# KMT1-42_CPU_rev_2_0_0.net
KiCad netlist of a schematic drawn in Altium Designer
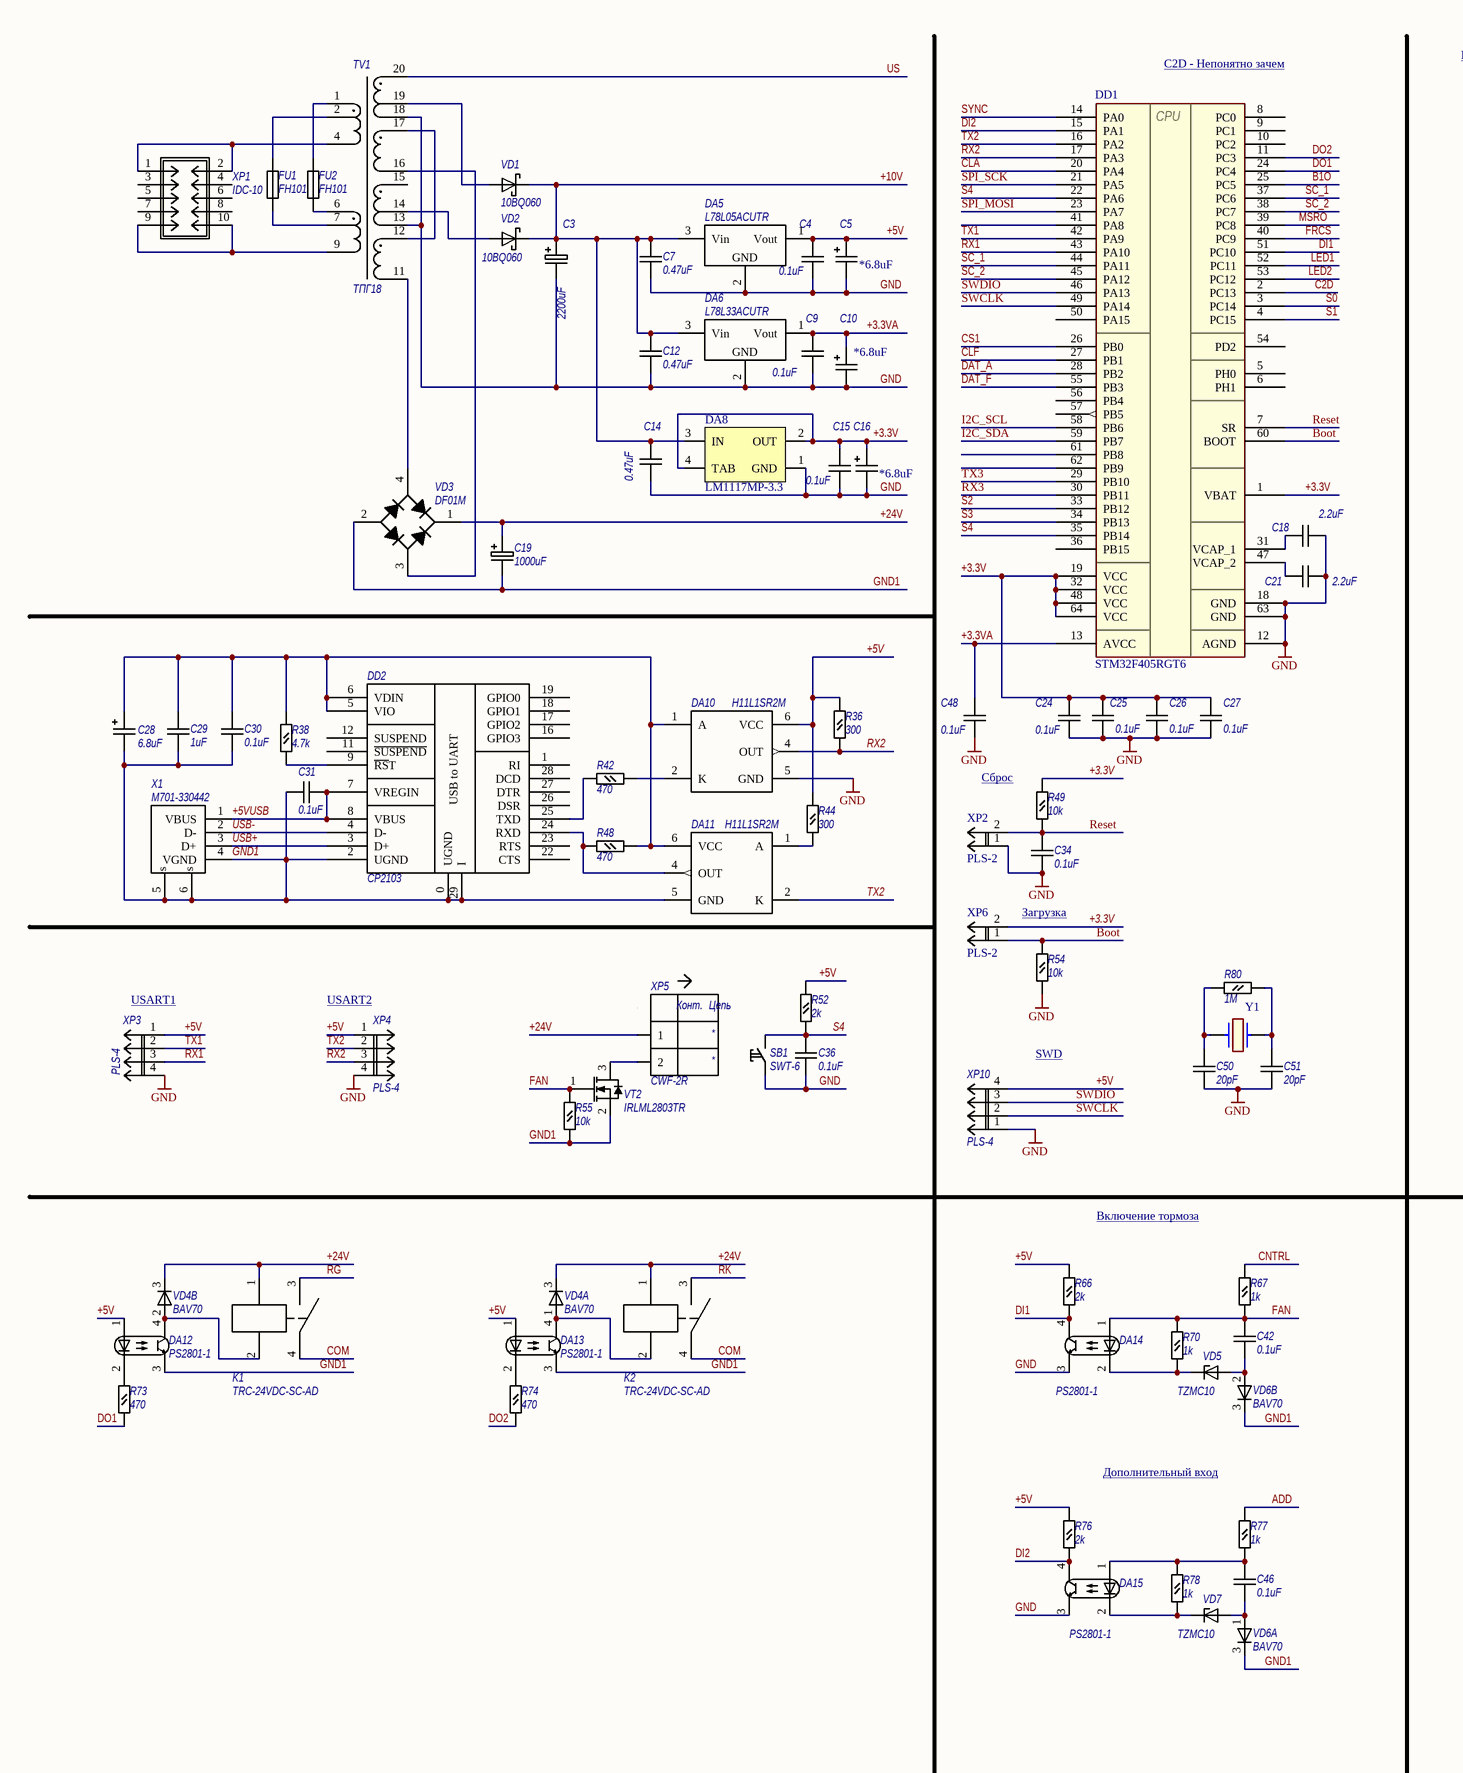
[diagram p0: KMT1-42.CPU rev.2.0.0.SchDoc, left]
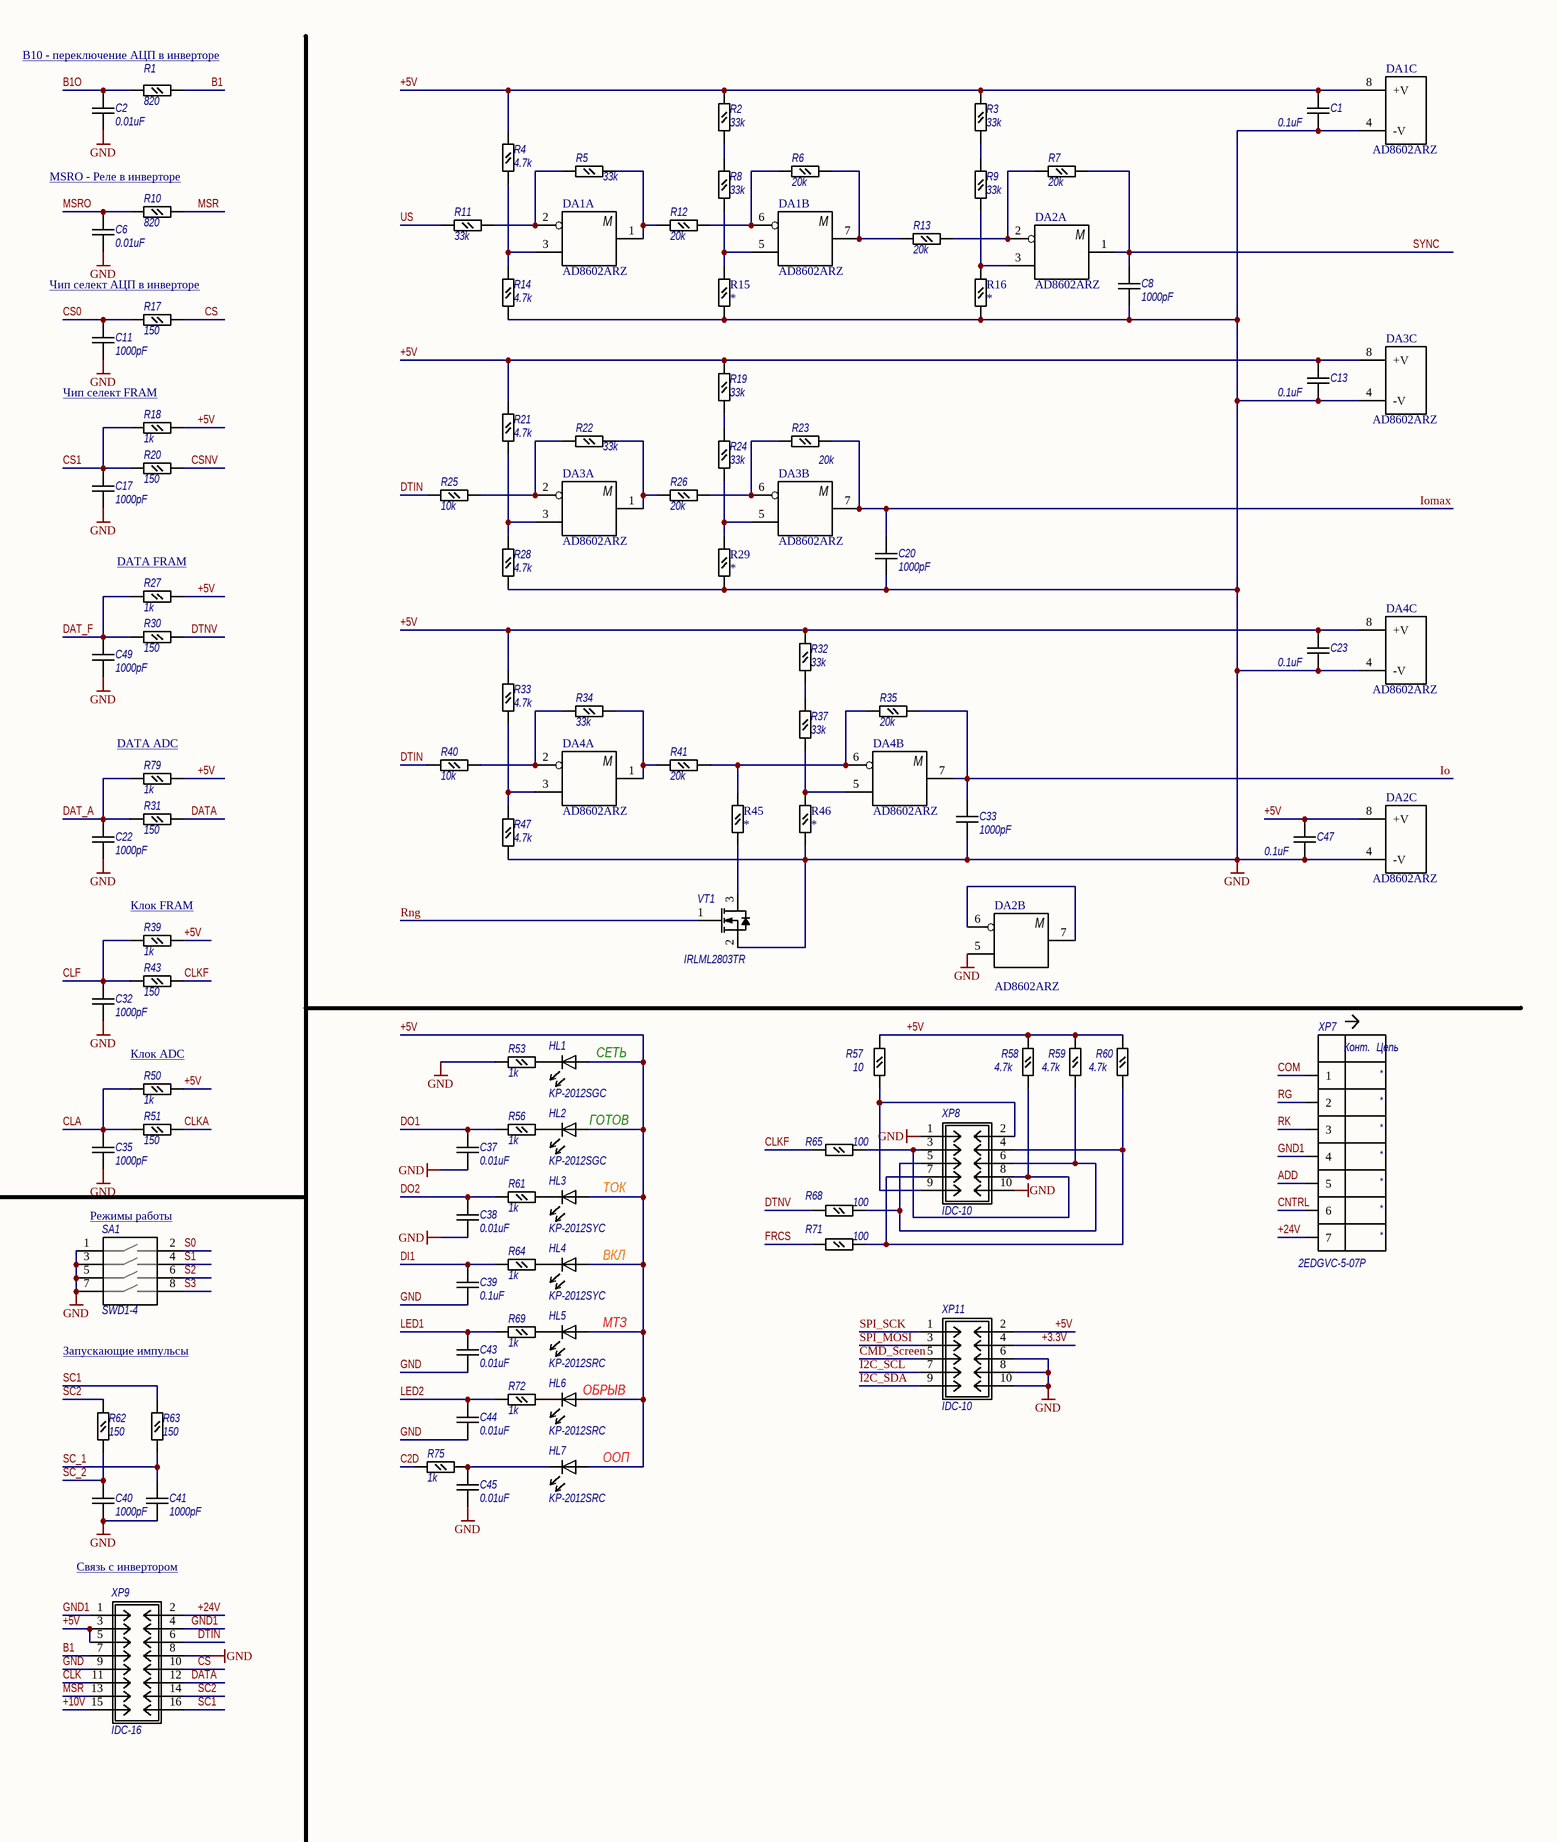
[diagram p1: KMT1-42.CPU rev.2.0.0.SchDoc, right]

(export (version "E")
  (design (tool "Eeschema 10.0.6"))
  (components
    (comp (ref "C1")
      (value "0.1uF")
      (footprint "cap0805")
      (description "Керамический конденсатор, SMD")
      (fields
        (field (name "PART NUMBER") "cap0805")
        (field (name "VALUESCH") "0.1uF")
        (field (name "TOLERANCE") "X7R")
      )
      (libsource (lib "db_imd") (part "Cap"))
    )
    (comp (ref "C2")
      (value "0.01uF")
      (footprint "cap0805")
      (description "Керамический конденсатор, SMD")
      (fields
        (field (name "PART NUMBER") "cap0805")
        (field (name "VALUESCH") "0.01uF")
        (field (name "TOLERANCE") "X7R")
      )
      (libsource (lib "db_imd") (part "Cap"))
    )
    (comp (ref "C3")
      (value "2200uF")
      (footprint "ECR-EHR 13mm")
      (description "Алюминиевый конденсатор Hitano")
      (fields
        (field (name "PART NUMBER") "ECR/EHR/EXR D=13mm")
        (field (name "VALUESCH") "2200uF")
        (field (name "VOLTAGE") "16V")
      )
      (libsource (lib "db_imd") (part "cap_elect_pol"))
    )
    (comp (ref "C4")
      (value "0.1uF")
      (footprint "cap0805")
      (description "Керамический конденсатор, SMD")
      (fields
        (field (name "PART NUMBER") "cap0805")
        (field (name "VALUESCH") "0.1uF")
        (field (name "TOLERANCE") "X7R")
      )
      (libsource (lib "db_imd") (part "Cap"))
    )
    (comp (ref "C5")
      (value "*6.8uF")
      (footprint "TC3216-1206-A")
      (description "Танталовый конденсатор, SMD")
      (fields (field (name "PART NUMBER") "capA") (field (name "VALUESCH") "*6.8uF"))
      (libsource (lib "db_imd") (part "Cap_el"))
    )
    (comp (ref "C6")
      (value "0.01uF")
      (footprint "cap0805")
      (description "Керамический конденсатор, SMD")
      (fields
        (field (name "PART NUMBER") "cap0805")
        (field (name "VALUESCH") "0.01uF")
        (field (name "TOLERANCE") "X7R")
      )
      (libsource (lib "db_imd") (part "Cap"))
    )
    (comp (ref "C7")
      (value "0.47uF")
      (footprint "cap0805")
      (description "Керамический конденсатор, SMD")
      (fields
        (field (name "PART NUMBER") "cap0805")
        (field (name "VALUESCH") "0.47uF")
        (field (name "TOLERANCE") "X7R")
      )
      (libsource (lib "db_imd") (part "Cap"))
    )
    (comp (ref "C8")
      (value "1000pF")
      (footprint "cap0805")
      (description "Керамический конденсатор, SMD")
      (fields
        (field (name "PART NUMBER") "cap0805")
        (field (name "VALUESCH") "1000pF")
        (field (name "TOLERANCE") "X7R")
      )
      (libsource (lib "db_imd") (part "Cap"))
    )
    (comp (ref "C9")
      (value "0.1uF")
      (footprint "cap0805")
      (description "Керамический конденсатор, SMD")
      (fields
        (field (name "PART NUMBER") "cap0805")
        (field (name "VALUESCH") "0.1uF")
        (field (name "TOLERANCE") "X7R")
      )
      (libsource (lib "db_imd") (part "Cap"))
    )
    (comp (ref "C10")
      (value "*6.8uF")
      (footprint "TC3216-1206-A")
      (description "Танталовый конденсатор, SMD")
      (fields (field (name "PART NUMBER") "capA") (field (name "VALUESCH") "*6.8uF"))
      (libsource (lib "db_imd") (part "Cap_el"))
    )
    (comp (ref "C11")
      (value "1000pF")
      (footprint "cap0805")
      (description "Керамический конденсатор, SMD")
      (fields
        (field (name "PART NUMBER") "cap0805")
        (field (name "VALUESCH") "1000pF")
        (field (name "TOLERANCE") "X7R")
      )
      (libsource (lib "db_imd") (part "Cap"))
    )
    (comp (ref "C12")
      (value "0.47uF")
      (footprint "cap0805")
      (description "Керамический конденсатор, SMD")
      (fields
        (field (name "PART NUMBER") "cap0805")
        (field (name "VALUESCH") "0.47uF")
        (field (name "TOLERANCE") "X7R")
      )
      (libsource (lib "db_imd") (part "Cap"))
    )
    (comp (ref "C13")
      (value "0.1uF")
      (footprint "cap0805")
      (description "Керамический конденсатор, SMD")
      (fields
        (field (name "PART NUMBER") "cap0805")
        (field (name "VALUESCH") "0.1uF")
        (field (name "TOLERANCE") "X7R")
      )
      (libsource (lib "db_imd") (part "Cap"))
    )
    (comp (ref "C14")
      (value "0.47uF")
      (footprint "cap0805")
      (description "Керамический конденсатор, SMD")
      (fields
        (field (name "PART NUMBER") "cap0805")
        (field (name "VALUESCH") "0.47uF")
        (field (name "TOLERANCE") "X7R")
      )
      (libsource (lib "db_imd") (part "Cap"))
    )
    (comp (ref "C15")
      (value "0.1uF")
      (footprint "cap0805")
      (description "Керамический конденсатор, SMD")
      (fields
        (field (name "PART NUMBER") "cap0805")
        (field (name "VALUESCH") "0.1uF")
        (field (name "TOLERANCE") "X7R")
      )
      (libsource (lib "db_imd") (part "Cap"))
    )
    (comp (ref "C16")
      (value "*6.8uF")
      (footprint "TC3216-1206-A")
      (description "Танталовый конденсатор, SMD")
      (fields (field (name "PART NUMBER") "capA") (field (name "VALUESCH") "*6.8uF"))
      (libsource (lib "db_imd") (part "Cap_el"))
    )
    (comp (ref "C17")
      (value "1000pF")
      (footprint "cap0805")
      (description "Керамический конденсатор, SMD")
      (fields
        (field (name "PART NUMBER") "cap0805")
        (field (name "VALUESCH") "1000pF")
        (field (name "TOLERANCE") "X7R")
      )
      (libsource (lib "db_imd") (part "Cap"))
    )
    (comp (ref "C18")
      (value "2.2uF")
      (footprint "cap0805")
      (description "Керамический конденсатор, SMD")
      (fields
        (field (name "PART NUMBER") "cap0805")
        (field (name "VALUESCH") "2.2uF")
        (field (name "TOLERANCE") "X7R")
      )
      (libsource (lib "db_imd") (part "Cap"))
    )
    (comp (ref "C19")
      (value "1000uF")
      (footprint "ECR-EHR 13mm")
      (description "Алюминиевый конденсатор Hitano")
      (fields
        (field (name "PART NUMBER") "ECR/EHR/EXR D=13mm")
        (field (name "VALUESCH") "1000uF")
        (field (name "VOLTAGE") "35V")
      )
      (libsource (lib "db_imd") (part "cap_elect_pol"))
    )
    (comp (ref "C20")
      (value "1000pF")
      (footprint "cap0805")
      (description "Керамический конденсатор, SMD")
      (fields
        (field (name "PART NUMBER") "cap0805")
        (field (name "VALUESCH") "1000pF")
        (field (name "TOLERANCE") "X7R")
      )
      (libsource (lib "db_imd") (part "Cap"))
    )
    (comp (ref "C21")
      (value "2.2uF")
      (footprint "cap0805")
      (description "Керамический конденсатор, SMD")
      (fields
        (field (name "PART NUMBER") "cap0805")
        (field (name "VALUESCH") "2.2uF")
        (field (name "TOLERANCE") "X7R")
      )
      (libsource (lib "db_imd") (part "Cap"))
    )
    (comp (ref "C22")
      (value "1000pF")
      (footprint "cap0805")
      (description "Керамический конденсатор, SMD")
      (fields
        (field (name "PART NUMBER") "cap0805")
        (field (name "VALUESCH") "1000pF")
        (field (name "TOLERANCE") "X7R")
      )
      (libsource (lib "db_imd") (part "Cap"))
    )
    (comp (ref "C23")
      (value "0.1uF")
      (footprint "cap0805")
      (description "Керамический конденсатор, SMD")
      (fields
        (field (name "PART NUMBER") "cap0805")
        (field (name "VALUESCH") "0.1uF")
        (field (name "TOLERANCE") "X7R")
      )
      (libsource (lib "db_imd") (part "Cap"))
    )
    (comp (ref "C24")
      (value "0.1uF")
      (footprint "cap0805")
      (description "Керамический конденсатор, SMD")
      (fields
        (field (name "PART NUMBER") "cap0805")
        (field (name "VALUESCH") "0.1uF")
        (field (name "TOLERANCE") "X7R")
      )
      (libsource (lib "db_imd") (part "Cap"))
    )
    (comp (ref "C25")
      (value "0.1uF")
      (footprint "cap0805")
      (description "Керамический конденсатор, SMD")
      (fields
        (field (name "PART NUMBER") "cap0805")
        (field (name "VALUESCH") "0.1uF")
        (field (name "TOLERANCE") "X7R")
      )
      (libsource (lib "db_imd") (part "Cap"))
    )
    (comp (ref "C26")
      (value "0.1uF")
      (footprint "cap0805")
      (description "Керамический конденсатор, SMD")
      (fields
        (field (name "PART NUMBER") "cap0805")
        (field (name "VALUESCH") "0.1uF")
        (field (name "TOLERANCE") "X7R")
      )
      (libsource (lib "db_imd") (part "Cap"))
    )
    (comp (ref "C27")
      (value "0.1uF")
      (footprint "cap0805")
      (description "Керамический конденсатор, SMD")
      (fields
        (field (name "PART NUMBER") "cap0805")
        (field (name "VALUESCH") "0.1uF")
        (field (name "TOLERANCE") "X7R")
      )
      (libsource (lib "db_imd") (part "Cap"))
    )
    (comp (ref "C28")
      (value "6.8uF")
      (footprint "TC3216-1206-A")
      (description "Танталовый конденсатор, SMD")
      (fields
        (field (name "PART NUMBER") "capA")
        (field (name "VALUESCH") "6.8uF")
        (field (name "VOLTAGE") "6.3V")
      )
      (libsource (lib "db_imd") (part "Cap_el"))
    )
    (comp (ref "C29")
      (value "1uF")
      (footprint "cap0805")
      (description "Керамический конденсатор, SMD")
      (fields
        (field (name "PART NUMBER") "cap0805")
        (field (name "VALUESCH") "1uF")
        (field (name "TOLERANCE") "X7R")
      )
      (libsource (lib "db_imd") (part "Cap"))
    )
    (comp (ref "C30")
      (value "0.1uF")
      (footprint "cap0805")
      (description "Керамический конденсатор, SMD")
      (fields
        (field (name "PART NUMBER") "cap0805")
        (field (name "VALUESCH") "0.1uF")
        (field (name "TOLERANCE") "X7R")
      )
      (libsource (lib "db_imd") (part "Cap"))
    )
    (comp (ref "C31")
      (value "0.1uF")
      (footprint "cap0805")
      (description "Керамический конденсатор, SMD")
      (fields
        (field (name "PART NUMBER") "cap0805")
        (field (name "VALUESCH") "0.1uF")
        (field (name "TOLERANCE") "X7R")
      )
      (libsource (lib "db_imd") (part "Cap"))
    )
    (comp (ref "C32")
      (value "1000pF")
      (footprint "cap0805")
      (description "Керамический конденсатор, SMD")
      (fields
        (field (name "PART NUMBER") "cap0805")
        (field (name "VALUESCH") "1000pF")
        (field (name "TOLERANCE") "X7R")
      )
      (libsource (lib "db_imd") (part "Cap"))
    )
    (comp (ref "C33")
      (value "1000pF")
      (footprint "cap0805")
      (description "Керамический конденсатор, SMD")
      (fields
        (field (name "PART NUMBER") "cap0805")
        (field (name "VALUESCH") "1000pF")
        (field (name "TOLERANCE") "X7R")
      )
      (libsource (lib "db_imd") (part "Cap"))
    )
    (comp (ref "C34")
      (value "0.1uF")
      (footprint "cap0805")
      (description "Керамический конденсатор, SMD")
      (fields
        (field (name "PART NUMBER") "cap0805")
        (field (name "VALUESCH") "0.1uF")
        (field (name "TOLERANCE") "X7R")
      )
      (libsource (lib "db_imd") (part "Cap"))
    )
    (comp (ref "C35")
      (value "1000pF")
      (footprint "cap0805")
      (description "Керамический конденсатор, SMD")
      (fields
        (field (name "PART NUMBER") "cap0805")
        (field (name "VALUESCH") "1000pF")
        (field (name "TOLERANCE") "X7R")
      )
      (libsource (lib "db_imd") (part "Cap"))
    )
    (comp (ref "C36")
      (value "0.1uF")
      (footprint "cap0805")
      (description "Керамический конденсатор, SMD")
      (fields
        (field (name "PART NUMBER") "cap0805")
        (field (name "VALUESCH") "0.1uF")
        (field (name "TOLERANCE") "X7R")
      )
      (libsource (lib "db_imd") (part "Cap"))
    )
    (comp (ref "C37")
      (value "0.01uF")
      (footprint "cap0805")
      (description "Керамический конденсатор, SMD")
      (fields
        (field (name "PART NUMBER") "cap0805")
        (field (name "VALUESCH") "0.01uF")
        (field (name "TOLERANCE") "X7R")
      )
      (libsource (lib "db_imd") (part "Cap"))
    )
    (comp (ref "C38")
      (value "0.01uF")
      (footprint "cap0805")
      (description "Керамический конденсатор, SMD")
      (fields
        (field (name "PART NUMBER") "cap0805")
        (field (name "VALUESCH") "0.01uF")
        (field (name "TOLERANCE") "X7R")
      )
      (libsource (lib "db_imd") (part "Cap"))
    )
    (comp (ref "C39")
      (value "0.1uF")
      (footprint "cap0805")
      (description "Керамический конденсатор, SMD")
      (fields
        (field (name "PART NUMBER") "cap0805")
        (field (name "VALUESCH") "0.1uF")
        (field (name "TOLERANCE") "X7R")
      )
      (libsource (lib "db_imd") (part "Cap"))
    )
    (comp (ref "C40")
      (value "1000pF")
      (footprint "cap0805")
      (description "Керамический конденсатор, SMD")
      (fields
        (field (name "PART NUMBER") "cap0805")
        (field (name "VALUESCH") "1000pF")
        (field (name "TOLERANCE") "X7R")
      )
      (libsource (lib "db_imd") (part "Cap"))
    )
    (comp (ref "C41")
      (value "1000pF")
      (footprint "cap0805")
      (description "Керамический конденсатор, SMD")
      (fields
        (field (name "PART NUMBER") "cap0805")
        (field (name "VALUESCH") "1000pF")
        (field (name "TOLERANCE") "X7R")
      )
      (libsource (lib "db_imd") (part "Cap"))
    )
    (comp (ref "C42")
      (value "0.1uF")
      (footprint "cap0805")
      (description "Керамический конденсатор, SMD")
      (fields
        (field (name "PART NUMBER") "cap0805")
        (field (name "VALUESCH") "0.1uF")
        (field (name "TOLERANCE") "X7R")
      )
      (libsource (lib "db_imd") (part "Cap"))
    )
    (comp (ref "C43")
      (value "0.01uF")
      (footprint "cap0805")
      (description "Керамический конденсатор, SMD")
      (fields
        (field (name "PART NUMBER") "cap0805")
        (field (name "VALUESCH") "0.01uF")
        (field (name "TOLERANCE") "X7R")
      )
      (libsource (lib "db_imd") (part "Cap"))
    )
    (comp (ref "C44")
      (value "0.01uF")
      (footprint "cap0805")
      (description "Керамический конденсатор, SMD")
      (fields
        (field (name "PART NUMBER") "cap0805")
        (field (name "VALUESCH") "0.01uF")
        (field (name "TOLERANCE") "X7R")
      )
      (libsource (lib "db_imd") (part "Cap"))
    )
    (comp (ref "C45")
      (value "0.01uF")
      (footprint "cap0805")
      (description "Керамический конденсатор, SMD")
      (fields
        (field (name "PART NUMBER") "cap0805")
        (field (name "VALUESCH") "0.01uF")
        (field (name "TOLERANCE") "X7R")
      )
      (libsource (lib "db_imd") (part "Cap"))
    )
    (comp (ref "C46")
      (value "0.1uF")
      (footprint "cap0805")
      (description "Керамический конденсатор, SMD")
      (fields
        (field (name "PART NUMBER") "cap0805")
        (field (name "VALUESCH") "0.1uF")
        (field (name "TOLERANCE") "X7R")
      )
      (libsource (lib "db_imd") (part "Cap"))
    )
    (comp (ref "C47")
      (value "0.1uF")
      (footprint "cap0805")
      (description "Керамический конденсатор, SMD")
      (fields
        (field (name "PART NUMBER") "cap0805")
        (field (name "VALUESCH") "0.1uF")
        (field (name "TOLERANCE") "X7R")
      )
      (libsource (lib "db_imd") (part "Cap"))
    )
    (comp (ref "C48")
      (value "0.1uF")
      (footprint "cap0805")
      (description "Керамический конденсатор, SMD")
      (fields
        (field (name "PART NUMBER") "cap0805")
        (field (name "VALUESCH") "0.1uF")
        (field (name "TOLERANCE") "X7R")
      )
      (libsource (lib "db_imd") (part "Cap"))
    )
    (comp (ref "C49")
      (value "1000pF")
      (footprint "cap0805")
      (description "Керамический конденсатор, SMD")
      (fields
        (field (name "PART NUMBER") "cap0805")
        (field (name "VALUESCH") "1000pF")
        (field (name "TOLERANCE") "X7R")
      )
      (libsource (lib "db_imd") (part "Cap"))
    )
    (comp (ref "C50")
      (value "20pF")
      (footprint "cap0805")
      (description "Керамический конденсатор, SMD")
      (fields
        (field (name "PART NUMBER") "cap0805")
        (field (name "VALUESCH") "20pF")
        (field (name "TOLERANCE") "X7R")
      )
      (libsource (lib "db_imd") (part "Cap"))
    )
    (comp (ref "C51")
      (value "20pF")
      (footprint "cap0805")
      (description "Керамический конденсатор, SMD")
      (fields
        (field (name "PART NUMBER") "cap0805")
        (field (name "VALUESCH") "20pF")
        (field (name "TOLERANCE") "X7R")
      )
      (libsource (lib "db_imd") (part "Cap"))
    )
    (comp (ref "DA1")
      (value "AD8602ARZ")
      (footprint "SO-8")
      (description "Операционный усилитель 2 в 1")
      (fields (field (name "VALUESCH") "AD8602ARZ"))
      (libsource (lib "db_imd") (part "Opamp2x1"))
    )
    (comp (ref "DA2")
      (value "AD8602ARZ")
      (footprint "SO-8")
      (description "Операционный усилитель 2 в 1")
      (fields (field (name "VALUESCH") "AD8602ARZ"))
      (libsource (lib "db_imd") (part "Opamp2x1"))
    )
    (comp (ref "DA3")
      (value "AD8602ARZ")
      (footprint "SO-8")
      (description "Операционный усилитель 2 в 1")
      (fields (field (name "VALUESCH") "AD8602ARZ"))
      (libsource (lib "db_imd") (part "Opamp2x1"))
    )
    (comp (ref "DA4")
      (value "AD8602ARZ")
      (footprint "SO-8")
      (description "Операционный усилитель 2 в 1")
      (fields (field (name "VALUESCH") "AD8602ARZ"))
      (libsource (lib "db_imd") (part "Opamp2x1"))
    )
    (comp (ref "DA5")
      (value "L78L05ACUTR")
      (footprint "SOT89")
      (description "Линейный стабилизатор 5V")
      (fields (field (name "VALUESCH") "L78L05ACUTR"))
      (libsource (lib "db_imd") (part "L78L00"))
    )
    (comp (ref "DA6")
      (value "L78L33ACUTR")
      (footprint "SOT89")
      (description "Линейный стабилизатор 3.3V")
      (fields (field (name "VALUESCH") "L78L33ACUTR"))
      (libsource (lib "db_imd") (part "L78L00"))
    )
    (comp (ref "DA8")
      (value "LM1117MP-3.3")
      (footprint "SOT223")
      (description "Линейный стабилизатор 3.3V")
      (fields (field (name "VALUESCH") "LM1117MP-3.3"))
      (libsource (lib "db_intmash") (part "LM1117-3.3"))
    )
    (comp (ref "DA10")
      (value "H11L1SR2M")
      (footprint "PDIP6")
      (description "Оптопара 1 Мбит")
      (fields (field (name "VALUESCH") "H11L1SR2M"))
      (libsource (lib "db_imd") (part "H11L1SR2M"))
    )
    (comp (ref "DA11")
      (value "H11L1SR2M")
      (footprint "PDIP6")
      (description "Оптопара 1 Мбит")
      (fields (field (name "VALUESCH") "H11L1SR2M"))
      (libsource (lib "") (part "H11L1SR2M_1"))
    )
    (comp (ref "DA12")
      (value "PS2801-1")
      (footprint "SOP4")
      (description "Оптопара")
      (fields (field (name "VALUESCH") "PS2801-1"))
      (libsource (lib "") (part "PS2801-1_1"))
    )
    (comp (ref "DA13")
      (value "PS2801-1")
      (footprint "SOP4")
      (description "Оптопара")
      (fields (field (name "VALUESCH") "PS2801-1"))
      (libsource (lib "") (part "PS2801-1_1"))
    )
    (comp (ref "DA14")
      (value "PS2801-1")
      (footprint "SOP4")
      (description "Оптопара")
      (fields (field (name "VALUESCH") "PS2801-1"))
      (libsource (lib "db_imd") (part "PS2801-1"))
    )
    (comp (ref "DA15")
      (value "PS2801-1")
      (footprint "SOP4")
      (description "Оптопара")
      (fields (field (name "VALUESCH") "PS2801-1"))
      (libsource (lib "db_imd") (part "PS2801-1"))
    )
    (comp (ref "DD1")
      (value "STM32F405RGT6")
      (footprint "LQFP64")
      (description "Микроконтроллер 32 бит CORTEX M4")
      (fields (field (name "VALUESCH") "STM32F405RGT6"))
      (libsource (lib "db_imd") (part "STM32F405RGT6"))
    )
    (comp (ref "DD2")
      (value "CP2103")
      (footprint "QFN-28")
      (description "Чип USB -> UART")
      (fields (field (name "VALUESCH") "CP2103"))
      (libsource (lib "db_imd") (part "CP2103"))
    )
    (comp (ref "FU1")
      (value "FH101")
      (footprint "FH101")
      (description "Держатель для предохранителей 250В 5А")
      (fields (field (name "VALUESCH") "FH101"))
      (libsource (lib "db_imd") (part "FUSE"))
    )
    (comp (ref "FU2")
      (value "FH101")
      (footprint "FH101")
      (description "Держатель для предохранителей 250В 5А")
      (fields (field (name "VALUESCH") "FH101"))
      (libsource (lib "db_imd") (part "FUSE"))
    )
    (comp (ref "HL1")
      (value "KP-2012SGC")
      (footprint "Led0805")
      (description "SMD светодиод зеленый")
      (fields (field (name "VALUESCH") "KP-2012SGC"))
      (libsource (lib "db_imd") (part "LED"))
    )
    (comp (ref "HL2")
      (value "KP-2012SGC")
      (footprint "Led0805")
      (description "SMD светодиод зеленый")
      (fields (field (name "VALUESCH") "KP-2012SGC"))
      (libsource (lib "db_imd") (part "LED"))
    )
    (comp (ref "HL3")
      (value "KP-2012SYC")
      (footprint "Led0805")
      (description "SMD светодиод желтый")
      (fields (field (name "VALUESCH") "KP-2012SYC"))
      (libsource (lib "db_imd") (part "LED"))
    )
    (comp (ref "HL4")
      (value "KP-2012SYC")
      (footprint "Led0805")
      (description "SMD светодиод желтый")
      (fields (field (name "VALUESCH") "KP-2012SYC"))
      (libsource (lib "db_imd") (part "LED"))
    )
    (comp (ref "HL5")
      (value "KP-2012SRC")
      (footprint "Led0805")
      (description "SMD светодиод красный")
      (fields (field (name "VALUESCH") "KP-2012SRC"))
      (libsource (lib "db_imd") (part "LED"))
    )
    (comp (ref "HL6")
      (value "KP-2012SRC")
      (footprint "Led0805")
      (description "SMD светодиод красный")
      (fields (field (name "VALUESCH") "KP-2012SRC"))
      (libsource (lib "db_imd") (part "LED"))
    )
    (comp (ref "HL7")
      (value "KP-2012SRC")
      (footprint "Led0805")
      (description "SMD светодиод красный")
      (fields (field (name "VALUESCH") "KP-2012SRC"))
      (libsource (lib "db_imd") (part "LED"))
    )
    (comp (ref "K1")
      (value "TRC-24VDC-SC-AD")
      (footprint "TRC-24VDC-SC-AD")
      (description "Реле электромагнитное 24В 10А, 1 контакт (SPST)")
      (fields (field (name "VALUESCH") "TRC-24VDC-SC-AD"))
      (libsource (lib "db_imd") (part "SPST"))
    )
    (comp (ref "K2")
      (value "TRC-24VDC-SC-AD")
      (footprint "TRC-24VDC-SC-AD")
      (description "Реле электромагнитное 24В 10А, 1 контакт (SPST)")
      (fields (field (name "VALUESCH") "TRC-24VDC-SC-AD"))
      (libsource (lib "db_imd") (part "SPST"))
    )
    (comp (ref "R1")
      (value "820")
      (footprint "res0805")
      (description "Резистор 0.125 W, SMD")
      (fields (field (name "PART NUMBER") "res0805") (field (name "VALUESCH") "820"))
      (libsource (lib "db_imd") (part "res_0.125W"))
    )
    (comp (ref "R2")
      (value "33k")
      (footprint "res0805")
      (description "Резистор 0.125 W, SMD")
      (fields (field (name "PART NUMBER") "res0805") (field (name "VALUESCH") "33k"))
      (libsource (lib "") (part "res_0.125W_3"))
    )
    (comp (ref "R3")
      (value "33k")
      (footprint "res0805")
      (description "Резистор 0.125 W, SMD")
      (fields (field (name "PART NUMBER") "res0805") (field (name "VALUESCH") "33k"))
      (libsource (lib "") (part "res_0.125W_3"))
    )
    (comp (ref "R4")
      (value "4.7k")
      (footprint "res0805")
      (description "Резистор 0.125 W, SMD")
      (fields (field (name "PART NUMBER") "res0805") (field (name "VALUESCH") "4.7k"))
      (libsource (lib "") (part "res_0.125W_3"))
    )
    (comp (ref "R5")
      (value "33k")
      (footprint "res0805")
      (description "Резистор 0.125 W, SMD")
      (fields (field (name "PART NUMBER") "res0805") (field (name "VALUESCH") "33k"))
      (libsource (lib "db_imd") (part "res_0.125W"))
    )
    (comp (ref "R6")
      (value "20k")
      (footprint "res0805")
      (description "Резистор 0.125 W, SMD")
      (fields (field (name "PART NUMBER") "res0805") (field (name "VALUESCH") "20k"))
      (libsource (lib "db_imd") (part "res_0.125W"))
    )
    (comp (ref "R7")
      (value "20k")
      (footprint "res0805")
      (description "Резистор 0.125 W, SMD")
      (fields (field (name "PART NUMBER") "res0805") (field (name "VALUESCH") "20k"))
      (libsource (lib "db_imd") (part "res_0.125W"))
    )
    (comp (ref "R8")
      (value "33k")
      (footprint "res0805")
      (description "Резистор 0.125 W, SMD")
      (fields (field (name "PART NUMBER") "res0805") (field (name "VALUESCH") "33k"))
      (libsource (lib "") (part "res_0.125W_3"))
    )
    (comp (ref "R9")
      (value "33k")
      (footprint "res0805")
      (description "Резистор 0.125 W, SMD")
      (fields (field (name "PART NUMBER") "res0805") (field (name "VALUESCH") "33k"))
      (libsource (lib "") (part "res_0.125W_3"))
    )
    (comp (ref "R10")
      (value "820")
      (footprint "res0805")
      (description "Резистор 0.125 W, SMD")
      (fields (field (name "PART NUMBER") "res0805") (field (name "VALUESCH") "820"))
      (libsource (lib "db_imd") (part "res_0.125W"))
    )
    (comp (ref "R11")
      (value "33k")
      (footprint "res0805")
      (description "Резистор 0.125 W, SMD")
      (fields (field (name "PART NUMBER") "res0805") (field (name "VALUESCH") "33k"))
      (libsource (lib "") (part "res_0.125W_1"))
    )
    (comp (ref "R12")
      (value "20k")
      (footprint "res0805")
      (description "Резистор 0.125 W, SMD")
      (fields (field (name "PART NUMBER") "res0805") (field (name "VALUESCH") "20k"))
      (libsource (lib "db_imd") (part "res_0.125W"))
    )
    (comp (ref "R13")
      (value "20k")
      (footprint "res0805")
      (description "Резистор 0.125 W, SMD")
      (fields (field (name "PART NUMBER") "res0805") (field (name "VALUESCH") "20k"))
      (libsource (lib "db_imd") (part "res_0.125W"))
    )
    (comp (ref "R14")
      (value "4.7k")
      (footprint "res0805")
      (description "Резистор 0.125 W, SMD")
      (fields (field (name "PART NUMBER") "res0805") (field (name "VALUESCH") "4.7k"))
      (libsource (lib "") (part "res_0.125W_3"))
    )
    (comp (ref "R15")
      (value "*")
      (footprint "res0805")
      (description "Резистор 0.125 W, SMD")
      (fields (field (name "PART NUMBER") "res0805") (field (name "VALUESCH") "*"))
      (libsource (lib "") (part "res_0.125W_2"))
    )
    (comp (ref "R16")
      (value "*")
      (footprint "res0805")
      (description "Резистор 0.125 W, SMD")
      (fields (field (name "PART NUMBER") "res0805") (field (name "VALUESCH") "*"))
      (libsource (lib "") (part "res_0.125W_2"))
    )
    (comp (ref "R17")
      (value "150")
      (footprint "res0805")
      (description "Резистор 0.125 W, SMD")
      (fields (field (name "PART NUMBER") "res0805") (field (name "VALUESCH") "150"))
      (libsource (lib "db_imd") (part "res_0.125W"))
    )
    (comp (ref "R18")
      (value "1k")
      (footprint "res0805")
      (description "Резистор 0.125 W, SMD")
      (fields (field (name "PART NUMBER") "res0805") (field (name "VALUESCH") "1k"))
      (libsource (lib "") (part "res_0.125W_1"))
    )
    (comp (ref "R19")
      (value "33k")
      (footprint "res0805")
      (description "Резистор 0.125 W, SMD")
      (fields (field (name "PART NUMBER") "res0805") (field (name "VALUESCH") "33k"))
      (libsource (lib "") (part "res_0.125W_3"))
    )
    (comp (ref "R20")
      (value "150")
      (footprint "res0805")
      (description "Резистор 0.125 W, SMD")
      (fields (field (name "PART NUMBER") "res0805") (field (name "VALUESCH") "150"))
      (libsource (lib "db_imd") (part "res_0.125W"))
    )
    (comp (ref "R21")
      (value "4.7k")
      (footprint "res0805")
      (description "Резистор 0.125 W, SMD")
      (fields (field (name "PART NUMBER") "res0805") (field (name "VALUESCH") "4.7k"))
      (libsource (lib "") (part "res_0.125W_3"))
    )
    (comp (ref "R22")
      (value "33k")
      (footprint "res0805")
      (description "Резистор 0.125 W, SMD")
      (fields (field (name "PART NUMBER") "res0805") (field (name "VALUESCH") "33k"))
      (libsource (lib "db_imd") (part "res_0.125W"))
    )
    (comp (ref "R23")
      (value "20k")
      (footprint "res0805")
      (description "Резистор 0.125 W, SMD")
      (fields (field (name "PART NUMBER") "res0805") (field (name "VALUESCH") "20k"))
      (libsource (lib "db_imd") (part "res_0.125W"))
    )
    (comp (ref "R24")
      (value "33k")
      (footprint "res0805")
      (description "Резистор 0.125 W, SMD")
      (fields (field (name "PART NUMBER") "res0805") (field (name "VALUESCH") "33k"))
      (libsource (lib "") (part "res_0.125W_3"))
    )
    (comp (ref "R25")
      (value "10k")
      (footprint "res0805")
      (description "Резистор 0.125 W, SMD")
      (fields (field (name "PART NUMBER") "res0805") (field (name "VALUESCH") "10k"))
      (libsource (lib "db_imd") (part "res_0.125W"))
    )
    (comp (ref "R26")
      (value "20k")
      (footprint "res0805")
      (description "Резистор 0.125 W, SMD")
      (fields (field (name "PART NUMBER") "res0805") (field (name "VALUESCH") "20k"))
      (libsource (lib "db_imd") (part "res_0.125W"))
    )
    (comp (ref "R27")
      (value "1k")
      (footprint "res0805")
      (description "Резистор 0.125 W, SMD")
      (fields (field (name "PART NUMBER") "res0805") (field (name "VALUESCH") "1k"))
      (libsource (lib "") (part "res_0.125W_1"))
    )
    (comp (ref "R28")
      (value "4.7k")
      (footprint "res0805")
      (description "Резистор 0.125 W, SMD")
      (fields (field (name "PART NUMBER") "res0805") (field (name "VALUESCH") "4.7k"))
      (libsource (lib "") (part "res_0.125W_3"))
    )
    (comp (ref "R29")
      (value "*")
      (footprint "res0805")
      (description "Резистор 0.125 W, SMD")
      (fields (field (name "PART NUMBER") "res0805") (field (name "VALUESCH") "*"))
      (libsource (lib "") (part "res_0.125W_2"))
    )
    (comp (ref "R30")
      (value "150")
      (footprint "res0805")
      (description "Резистор 0.125 W, SMD")
      (fields (field (name "PART NUMBER") "res0805") (field (name "VALUESCH") "150"))
      (libsource (lib "db_imd") (part "res_0.125W"))
    )
    (comp (ref "R31")
      (value "150")
      (footprint "res0805")
      (description "Резистор 0.125 W, SMD")
      (fields (field (name "PART NUMBER") "res0805") (field (name "VALUESCH") "150"))
      (libsource (lib "db_imd") (part "res_0.125W"))
    )
    (comp (ref "R32")
      (value "33k")
      (footprint "res0805")
      (description "Резистор 0.125 W, SMD")
      (fields (field (name "PART NUMBER") "res0805") (field (name "VALUESCH") "33k"))
      (libsource (lib "") (part "res_0.125W_3"))
    )
    (comp (ref "R33")
      (value "4.7k")
      (footprint "res0805")
      (description "Резистор 0.125 W, SMD")
      (fields (field (name "PART NUMBER") "res0805") (field (name "VALUESCH") "4.7k"))
      (libsource (lib "") (part "res_0.125W_3"))
    )
    (comp (ref "R34")
      (value "33k")
      (footprint "res0805")
      (description "Резистор 0.125 W, SMD")
      (fields (field (name "PART NUMBER") "res0805") (field (name "VALUESCH") "33k"))
      (libsource (lib "db_imd") (part "res_0.125W"))
    )
    (comp (ref "R35")
      (value "20k")
      (footprint "res0805")
      (description "Резистор 0.125 W, SMD")
      (fields (field (name "PART NUMBER") "res0805") (field (name "VALUESCH") "20k"))
      (libsource (lib "db_imd") (part "res_0.125W"))
    )
    (comp (ref "R36")
      (value "300")
      (footprint "res0805")
      (description "Резистор 0.125 W, SMD")
      (fields (field (name "PART NUMBER") "res0805") (field (name "VALUESCH") "300"))
      (libsource (lib "") (part "res_0.125W_2"))
    )
    (comp (ref "R37")
      (value "33k")
      (footprint "res0805")
      (description "Резистор 0.125 W, SMD")
      (fields (field (name "PART NUMBER") "res0805") (field (name "VALUESCH") "33k"))
      (libsource (lib "") (part "res_0.125W_3"))
    )
    (comp (ref "R38")
      (value "4.7k")
      (footprint "res0805")
      (description "Резистор 0.125 W, SMD")
      (fields (field (name "PART NUMBER") "res0805") (field (name "VALUESCH") "4.7k"))
      (libsource (lib "") (part "res_0.125W_2"))
    )
    (comp (ref "R39")
      (value "1k")
      (footprint "res0805")
      (description "Резистор 0.125 W, SMD")
      (fields (field (name "PART NUMBER") "res0805") (field (name "VALUESCH") "1k"))
      (libsource (lib "") (part "res_0.125W_1"))
    )
    (comp (ref "R40")
      (value "10k")
      (footprint "res0805")
      (description "Резистор 0.125 W, SMD")
      (fields (field (name "PART NUMBER") "res0805") (field (name "VALUESCH") "10k"))
      (libsource (lib "db_imd") (part "res_0.125W"))
    )
    (comp (ref "R41")
      (value "20k")
      (footprint "res0805")
      (description "Резистор 0.125 W, SMD")
      (fields (field (name "PART NUMBER") "res0805") (field (name "VALUESCH") "20k"))
      (libsource (lib "db_imd") (part "res_0.125W"))
    )
    (comp (ref "R42")
      (value "470")
      (footprint "res0805")
      (description "Резистор 0.125 W, SMD")
      (fields (field (name "PART NUMBER") "res0805") (field (name "VALUESCH") "470"))
      (libsource (lib "") (part "res_0.125W_1"))
    )
    (comp (ref "R43")
      (value "150")
      (footprint "res0805")
      (description "Резистор 0.125 W, SMD")
      (fields (field (name "PART NUMBER") "res0805") (field (name "VALUESCH") "150"))
      (libsource (lib "db_imd") (part "res_0.125W"))
    )
    (comp (ref "R44")
      (value "300")
      (footprint "res0805")
      (description "Резистор 0.125 W, SMD")
      (fields (field (name "PART NUMBER") "res0805") (field (name "VALUESCH") "300"))
      (libsource (lib "") (part "res_0.125W_2"))
    )
    (comp (ref "R45")
      (value "*")
      (footprint "res0805")
      (description "Резистор 0.125 W, SMD")
      (fields (field (name "PART NUMBER") "res0805") (field (name "VALUESCH") "*"))
      (libsource (lib "") (part "res_0.125W_2"))
    )
    (comp (ref "R46")
      (value "*")
      (footprint "res0805")
      (description "Резистор 0.125 W, SMD")
      (fields (field (name "PART NUMBER") "res0805") (field (name "VALUESCH") "*"))
      (libsource (lib "") (part "res_0.125W_2"))
    )
    (comp (ref "R47")
      (value "4.7k")
      (footprint "res0805")
      (description "Резистор 0.125 W, SMD")
      (fields (field (name "PART NUMBER") "res0805") (field (name "VALUESCH") "4.7k"))
      (libsource (lib "") (part "res_0.125W_3"))
    )
    (comp (ref "R48")
      (value "470")
      (footprint "res0805")
      (description "Резистор 0.125 W, SMD")
      (fields (field (name "PART NUMBER") "res0805") (field (name "VALUESCH") "470"))
      (libsource (lib "") (part "res_0.125W_1"))
    )
    (comp (ref "R49")
      (value "10k")
      (footprint "res0805")
      (description "Резистор 0.125 W, SMD")
      (fields (field (name "PART NUMBER") "res0805") (field (name "VALUESCH") "10k"))
      (libsource (lib "") (part "res_0.125W_2"))
    )
    (comp (ref "R50")
      (value "1k")
      (footprint "res0805")
      (description "Резистор 0.125 W, SMD")
      (fields (field (name "PART NUMBER") "res0805") (field (name "VALUESCH") "1k"))
      (libsource (lib "") (part "res_0.125W_1"))
    )
    (comp (ref "R51")
      (value "150")
      (footprint "res0805")
      (description "Резистор 0.125 W, SMD")
      (fields (field (name "PART NUMBER") "res0805") (field (name "VALUESCH") "150"))
      (libsource (lib "db_imd") (part "res_0.125W"))
    )
    (comp (ref "R52")
      (value "2k")
      (footprint "res0805")
      (description "Резистор 0.125 W, SMD")
      (fields (field (name "PART NUMBER") "res0805") (field (name "VALUESCH") "2k"))
      (libsource (lib "") (part "res_0.125W_2"))
    )
    (comp (ref "R53")
      (value "1k")
      (footprint "res0805")
      (description "Резистор 0.125 W, SMD")
      (fields (field (name "PART NUMBER") "res0805") (field (name "VALUESCH") "1k"))
      (libsource (lib "db_imd") (part "res_0.125W"))
    )
    (comp (ref "R54")
      (value "10k")
      (footprint "res0805")
      (description "Резистор 0.125 W, SMD")
      (fields (field (name "PART NUMBER") "res0805") (field (name "VALUESCH") "10k"))
      (libsource (lib "") (part "res_0.125W_2"))
    )
    (comp (ref "R55")
      (value "10k")
      (footprint "res0805")
      (description "Резистор 0.125 W, SMD")
      (fields (field (name "PART NUMBER") "res0805") (field (name "VALUESCH") "10k"))
      (libsource (lib "") (part "res_0.125W_2"))
    )
    (comp (ref "R56")
      (value "1k")
      (footprint "res0805")
      (description "Резистор 0.125 W, SMD")
      (fields (field (name "PART NUMBER") "res0805") (field (name "VALUESCH") "1k"))
      (libsource (lib "db_imd") (part "res_0.125W"))
    )
    (comp (ref "R57")
      (value "10")
      (footprint "res0805")
      (description "Резистор 0.125 W, SMD")
      (fields (field (name "PART NUMBER") "res0805") (field (name "VALUESCH") "10"))
      (libsource (lib "") (part "res_0.125W_3"))
    )
    (comp (ref "R58")
      (value "4.7k")
      (footprint "res0805")
      (description "Резистор 0.125 W, SMD")
      (fields (field (name "PART NUMBER") "res0805") (field (name "VALUESCH") "4.7k"))
      (libsource (lib "") (part "res_0.125W_3"))
    )
    (comp (ref "R59")
      (value "4.7k")
      (footprint "res0805")
      (description "Резистор 0.125 W, SMD")
      (fields (field (name "PART NUMBER") "res0805") (field (name "VALUESCH") "4.7k"))
      (libsource (lib "") (part "res_0.125W_3"))
    )
    (comp (ref "R60")
      (value "4.7k")
      (footprint "res0805")
      (description "Резистор 0.125 W, SMD")
      (fields (field (name "PART NUMBER") "res0805") (field (name "VALUESCH") "4.7k"))
      (libsource (lib "") (part "res_0.125W_3"))
    )
    (comp (ref "R61")
      (value "1k")
      (footprint "res0805")
      (description "Резистор 0.125 W, SMD")
      (fields (field (name "PART NUMBER") "res0805") (field (name "VALUESCH") "1k"))
      (libsource (lib "db_imd") (part "res_0.125W"))
    )
    (comp (ref "R62")
      (value "150")
      (footprint "res0805")
      (description "Резистор 0.125 W, SMD")
      (fields (field (name "PART NUMBER") "res0805") (field (name "VALUESCH") "150"))
      (libsource (lib "") (part "res_0.125W_3"))
    )
    (comp (ref "R63")
      (value "150")
      (footprint "res0805")
      (description "Резистор 0.125 W, SMD")
      (fields (field (name "PART NUMBER") "res0805") (field (name "VALUESCH") "150"))
      (libsource (lib "") (part "res_0.125W_3"))
    )
    (comp (ref "R64")
      (value "1k")
      (footprint "res0805")
      (description "Резистор 0.125 W, SMD")
      (fields (field (name "PART NUMBER") "res0805") (field (name "VALUESCH") "1k"))
      (libsource (lib "db_imd") (part "res_0.125W"))
    )
    (comp (ref "R65")
      (value "100")
      (footprint "res0805")
      (description "Резистор 0.125 W, SMD")
      (fields (field (name "PART NUMBER") "res0805") (field (name "VALUESCH") "100"))
      (libsource (lib "") (part "res_0.125W_1"))
    )
    (comp (ref "R66")
      (value "2k")
      (footprint "res0805")
      (description "Резистор 0.125 W, SMD")
      (fields (field (name "PART NUMBER") "res0805") (field (name "VALUESCH") "2k"))
      (libsource (lib "") (part "res_0.125W_2"))
    )
    (comp (ref "R67")
      (value "1k")
      (footprint "res0805")
      (description "Резистор 0.125 W, SMD")
      (fields (field (name "PART NUMBER") "res0805") (field (name "VALUESCH") "1k"))
      (libsource (lib "") (part "res_0.125W_2"))
    )
    (comp (ref "R68")
      (value "100")
      (footprint "res0805")
      (description "Резистор 0.125 W, SMD")
      (fields (field (name "PART NUMBER") "res0805") (field (name "VALUESCH") "100"))
      (libsource (lib "") (part "res_0.125W_1"))
    )
    (comp (ref "R69")
      (value "1k")
      (footprint "res0805")
      (description "Резистор 0.125 W, SMD")
      (fields (field (name "PART NUMBER") "res0805") (field (name "VALUESCH") "1k"))
      (libsource (lib "db_imd") (part "res_0.125W"))
    )
    (comp (ref "R70")
      (value "1k")
      (footprint "res0805")
      (description "Резистор 0.125 W, SMD")
      (fields (field (name "PART NUMBER") "res0805") (field (name "VALUESCH") "1k"))
      (libsource (lib "") (part "res_0.125W_2"))
    )
    (comp (ref "R71")
      (value "100")
      (footprint "res0805")
      (description "Резистор 0.125 W, SMD")
      (fields (field (name "PART NUMBER") "res0805") (field (name "VALUESCH") "100"))
      (libsource (lib "") (part "res_0.125W_1"))
    )
    (comp (ref "R72")
      (value "1k")
      (footprint "res0805")
      (description "Резистор 0.125 W, SMD")
      (fields (field (name "PART NUMBER") "res0805") (field (name "VALUESCH") "1k"))
      (libsource (lib "db_imd") (part "res_0.125W"))
    )
    (comp (ref "R73")
      (value "470")
      (footprint "res0805")
      (description "Резистор 0.125 W, SMD")
      (fields (field (name "PART NUMBER") "res0805") (field (name "VALUESCH") "470"))
      (libsource (lib "") (part "res_0.125W_2"))
    )
    (comp (ref "R74")
      (value "470")
      (footprint "res0805")
      (description "Резистор 0.125 W, SMD")
      (fields (field (name "PART NUMBER") "res0805") (field (name "VALUESCH") "470"))
      (libsource (lib "") (part "res_0.125W_2"))
    )
    (comp (ref "R75")
      (value "1k")
      (footprint "res0805")
      (description "Резистор 0.125 W, SMD")
      (fields (field (name "PART NUMBER") "res0805") (field (name "VALUESCH") "1k"))
      (libsource (lib "db_imd") (part "res_0.125W"))
    )
    (comp (ref "R76")
      (value "2k")
      (footprint "res0805")
      (description "Резистор 0.125 W, SMD")
      (fields (field (name "PART NUMBER") "res0805") (field (name "VALUESCH") "2k"))
      (libsource (lib "") (part "res_0.125W_2"))
    )
    (comp (ref "R77")
      (value "1k")
      (footprint "res0805")
      (description "Резистор 0.125 W, SMD")
      (fields (field (name "PART NUMBER") "res0805") (field (name "VALUESCH") "1k"))
      (libsource (lib "") (part "res_0.125W_2"))
    )
    (comp (ref "R78")
      (value "1k")
      (footprint "res0805")
      (description "Резистор 0.125 W, SMD")
      (fields (field (name "PART NUMBER") "res0805") (field (name "VALUESCH") "1k"))
      (libsource (lib "") (part "res_0.125W_2"))
    )
    (comp (ref "R79")
      (value "1k")
      (footprint "res0805")
      (description "Резистор 0.125 W, SMD")
      (fields (field (name "PART NUMBER") "res0805") (field (name "VALUESCH") "1k"))
      (libsource (lib "") (part "res_0.125W_1"))
    )
    (comp (ref "R80")
      (value "1M")
      (footprint "res0805")
      (description "Резистор 0.125 W, SMD")
      (fields (field (name "PART NUMBER") "res0805") (field (name "VALUESCH") "1M"))
      (libsource (lib "") (part "res_0.125W_3"))
    )
    (comp (ref "SA1")
      (value "SWD1-4")
      (footprint "SWD1-4")
      (description "DIP - переключатель 4 шт.")
      (fields (field (name "VALUESCH") "SWD1-4"))
      (libsource (lib "db_imd") (part "SWD1-4"))
    )
    (comp (ref "SB1")
      (value "SWT-6")
      (footprint "SWT-6")
      (description "Кнопка тактовая 6 мм х 6 мм х 8мм")
      (fields (field (name "VALUESCH") "SWT-6"))
      (libsource (lib "db_imd") (part "SWT-6"))
    )
    (comp (ref "TV1")
      (value "ТПГ18")
      (footprint "TPG18")
      (description "Трансформатор ТПГ-18Вт")
      (fields (field (name "VALUESCH") "ТПГ18"))
      (libsource (lib "db_imd") (part "TPG18"))
    )
    (comp (ref "VD1")
      (value "10BQ060")
      (footprint "SMB")
      (description "Диод шоттки 60V 1A")
      (fields (field (name "VALUESCH") "10BQ060"))
      (libsource (lib "db_imd") (part "SHOTTKY"))
    )
    (comp (ref "VD2")
      (value "10BQ060")
      (footprint "SMB")
      (description "Диод шоттки 60V 1A")
      (fields (field (name "VALUESCH") "10BQ060"))
      (libsource (lib "db_imd") (part "SHOTTKY"))
    )
    (comp (ref "VD3")
      (value "DF01M")
      (footprint "DF-M")
      (description "Диодный мост 100V 1A")
      (fields (field (name "VALUESCH") "DF01M"))
      (libsource (lib "db_imd") (part "BRIDGE"))
    )
    (comp (ref "VD4")
      (value "BAV70")
      (footprint "SOT23")
      (description "Диодная сборка 2 в 1")
      (fields (field (name "VALUESCH") "BAV70"))
      (libsource (lib "db_imd") (part "BAV70"))
    )
    (comp (ref "VD5")
      (value "TZMC10")
      (footprint "SOD80")
      (description "Стабилитрон 10V")
      (fields (field (name "VALUESCH") "TZMC10"))
      (libsource (lib "db_imd") (part "ZENNER"))
    )
    (comp (ref "VD6")
      (value "BAV70")
      (footprint "SOT23")
      (description "Диодная сборка 2 в 1")
      (fields (field (name "VALUESCH") "BAV70"))
      (libsource (lib "db_imd") (part "BAV70"))
    )
    (comp (ref "VD7")
      (value "TZMC10")
      (footprint "SOD80")
      (description "Стабилитрон 10V")
      (fields (field (name "VALUESCH") "TZMC10"))
      (libsource (lib "db_imd") (part "ZENNER"))
    )
    (comp (ref "VT1")
      (value "IRLML2803TR")
      (footprint "SOT23")
      (description "N-канальный MOSFET 30В 1.2А")
      (fields (field (name "VALUESCH") "IRLML2803TR"))
      (libsource (lib "db_imd") (part "MOSFET-N23"))
    )
    (comp (ref "VT2")
      (value "IRLML2803TR")
      (footprint "SOT23")
      (description "N-канальный MOSFET 30В 1.2А")
      (fields (field (name "VALUESCH") "IRLML2803TR"))
      (libsource (lib "db_imd") (part "MOSFET-N23"))
    )
    (comp (ref "X1")
      (value "M701-330442")
      (footprint "USB_Bvert")
      (description "Разъём USB-B вертикальный")
      (fields (field (name "VALUESCH") "M701-330442"))
      (libsource (lib "db_imd") (part "USB_B"))
    )
    (comp (ref "XP1")
      (value "IDC-10")
      (footprint "IDC-10")
      (description "Вилка на плату 5х2 контактов шаг 2.54мм")
      (fields (field (name "VALUESCH") "IDC-10"))
      (libsource (lib "db_imd") (part "IDC-10"))
    )
    (comp (ref "XP2")
      (value "PLS-2")
      (footprint "PLS2")
      (description "Однорядный штыревой разъем 2 шаг 2.54мм")
      (fields (field (name "VALUESCH") "PLS-2"))
      (libsource (lib "db_imd") (part "PLS-2"))
    )
    (comp (ref "XP3")
      (value "PLS-4")
      (footprint "PLS4")
      (description "Однорядный штыревой разъем 4 шаг 2.54мм")
      (fields (field (name "VALUESCH") "PLS-4"))
      (libsource (lib "db_imd") (part "PLS-4"))
    )
    (comp (ref "XP4")
      (value "PLS-4")
      (footprint "PLS4")
      (description "Однорядный штыревой разъем 4 шаг 2.54мм")
      (fields (field (name "VALUESCH") "PLS-4"))
      (libsource (lib "db_imd") (part "PLS-4"))
    )
    (comp (ref "XP5")
      (value "CWF-2R")
      (footprint "CWF-2R")
      (description "Вилка на плату 2.50мм угловая закрытая")
      (fields (field (name "VALUESCH") "CWF-2R"))
      (libsource (lib "db_imd") (part "XP2_name"))
    )
    (comp (ref "XP6")
      (value "PLS-2")
      (footprint "PLS2")
      (description "Однорядный штыревой разъем 2 шаг 2.54мм")
      (fields (field (name "VALUESCH") "PLS-2"))
      (libsource (lib "db_imd") (part "PLS-2"))
    )
    (comp (ref "XP7")
      (value "2EDGVC-5-07P")
      (footprint "2EDGVC-5.0-7P-2")
      (description "Вилка на плату 7 конт. шаг 5мм")
      (fields (field (name "VALUESCH") "2EDGVC-5-07P"))
      (libsource (lib "db_imd") (part "XP7_name"))
    )
    (comp (ref "XP8")
      (value "IDC-10")
      (footprint "IDC-10")
      (description "Вилка на плату 5х2 контактов шаг 2.54мм")
      (fields (field (name "VALUESCH") "IDC-10"))
      (libsource (lib "db_imd") (part "IDC-10"))
    )
    (comp (ref "XP9")
      (value "IDC-16")
      (footprint "IDC-16")
      (description "Вилка на плату 8х2 контактов шаг 2.54мм")
      (fields (field (name "VALUESCH") "IDC-16"))
      (libsource (lib "db_imd") (part "IDC-16"))
    )
    (comp (ref "XP10")
      (value "PLS-4")
      (footprint "PLS4")
      (description "Однорядный штыревой разъем 4 шаг 2.54мм")
      (fields (field (name "VALUESCH") "PLS-4"))
      (libsource (lib "db_imd") (part "PLS-4"))
    )
    (comp (ref "XP11")
      (value "IDC-10")
      (footprint "IDC-10")
      (description "Вилка на плату 5х2 контактов шаг 2.54мм")
      (fields (field (name "VALUESCH") "IDC-10"))
      (libsource (lib "db_imd") (part "IDC-10"))
    )
    (comp (ref "Y1")
      (value "8 MHz")
      (footprint "XT49M")
      (description "Кварцевый осциллятор")
      (fields (field (name "PART NUMBER") "XT49M"))
      (libsource (lib "db_intmash") (part "Quartz_0"))
    )
  )
  (nets
    (net (code "1") (name "/+3.3V") (class "Default")
      (node (ref "C15") (pin "2") (pinfunction "2_2") (pintype "passive"))
      (node (ref "C16") (pin "1") (pinfunction "1_1") (pintype "passive"))
      (node (ref "C24") (pin "2") (pinfunction "2_2") (pintype "passive"))
      (node (ref "C25") (pin "2") (pinfunction "2_2") (pintype "passive"))
      (node (ref "C26") (pin "2") (pinfunction "2_2") (pintype "passive"))
      (node (ref "C27") (pin "2") (pinfunction "2_2") (pintype "passive"))
      (node (ref "DA8") (pin "2") (pinfunction "OUT_2") (pintype "passive"))
      (node (ref "DA8") (pin "4") (pinfunction "TAB_4") (pintype "passive"))
      (node (ref "DD1") (pin "1") (pinfunction "VBAT_1") (pintype "power_in"))
      (node (ref "DD1") (pin "19") (pinfunction "VCC_19") (pintype "passive"))
      (node (ref "DD1") (pin "32") (pinfunction "VCC_32") (pintype "passive"))
      (node (ref "DD1") (pin "48") (pinfunction "VCC_48") (pintype "passive"))
      (node (ref "DD1") (pin "64") (pinfunction "VCC_64") (pintype "passive"))
      (node (ref "R49") (pin "2") (pinfunction "2_2") (pintype "passive"))
      (node (ref "XP11") (pin "4") (pinfunction "4_4") (pintype "passive"))
      (node (ref "XP6") (pin "2") (pinfunction "2_2") (pintype "passive"))
    )
    (net (code "2") (name "/+3.3VA") (class "Default")
      (node (ref "C10") (pin "1") (pinfunction "1_1") (pintype "passive"))
      (node (ref "C48") (pin "2") (pinfunction "2_2") (pintype "passive"))
      (node (ref "C9") (pin "2") (pinfunction "2_2") (pintype "passive"))
      (node (ref "DA6") (pin "1") (pinfunction "Vout_1") (pintype "passive"))
      (node (ref "DD1") (pin "13") (pinfunction "AVCC_13") (pintype "power_in"))
    )
    (net (code "3") (name "/+5V") (class "Default")
      (node (ref "C1") (pin "2") (pinfunction "2_2") (pintype "passive"))
      (node (ref "C13") (pin "2") (pinfunction "2_2") (pintype "passive"))
      (node (ref "C23") (pin "2") (pinfunction "2_2") (pintype "passive"))
      (node (ref "C4") (pin "2") (pinfunction "2_2") (pintype "passive"))
      (node (ref "C47") (pin "2") (pinfunction "2_2") (pintype "passive"))
      (node (ref "C5") (pin "1") (pinfunction "1_1") (pintype "passive"))
      (node (ref "DA1") (pin "8") (pinfunction "+V_8") (pintype "power_in"))
      (node (ref "DA10") (pin "6") (pinfunction "VCC_6") (pintype "passive"))
      (node (ref "DA12") (pin "1") (pinfunction "A_1") (pintype "passive"))
      (node (ref "DA13") (pin "1") (pinfunction "A_1") (pintype "passive"))
      (node (ref "DA2") (pin "8") (pinfunction "+V_8") (pintype "power_in"))
      (node (ref "DA3") (pin "8") (pinfunction "+V_8") (pintype "power_in"))
      (node (ref "DA4") (pin "8") (pinfunction "+V_8") (pintype "power_in"))
      (node (ref "DA5") (pin "1") (pinfunction "Vout_1") (pintype "passive"))
      (node (ref "HL1") (pin "1") (pinfunction "A_1") (pintype "passive"))
      (node (ref "HL2") (pin "1") (pinfunction "A_1") (pintype "passive"))
      (node (ref "HL3") (pin "1") (pinfunction "A_1") (pintype "passive"))
      (node (ref "HL4") (pin "1") (pinfunction "A_1") (pintype "passive"))
      (node (ref "HL5") (pin "1") (pinfunction "A_1") (pintype "passive"))
      (node (ref "HL6") (pin "1") (pinfunction "A_1") (pintype "passive"))
      (node (ref "HL7") (pin "1") (pinfunction "A_1") (pintype "passive"))
      (node (ref "R18") (pin "2") (pinfunction "2_2") (pintype "passive"))
      (node (ref "R19") (pin "1") (pinfunction "1_1") (pintype "passive"))
      (node (ref "R2") (pin "1") (pinfunction "1_1") (pintype "passive"))
      (node (ref "R21") (pin "1") (pinfunction "1_1") (pintype "passive"))
      (node (ref "R27") (pin "2") (pinfunction "2_2") (pintype "passive"))
      (node (ref "R3") (pin "1") (pinfunction "1_1") (pintype "passive"))
      (node (ref "R32") (pin "1") (pinfunction "1_1") (pintype "passive"))
      (node (ref "R33") (pin "1") (pinfunction "1_1") (pintype "passive"))
      (node (ref "R36") (pin "2") (pinfunction "2_2") (pintype "passive"))
      (node (ref "R39") (pin "2") (pinfunction "2_2") (pintype "passive"))
      (node (ref "R4") (pin "1") (pinfunction "1_1") (pintype "passive"))
      (node (ref "R44") (pin "2") (pinfunction "2_2") (pintype "passive"))
      (node (ref "R50") (pin "2") (pinfunction "2_2") (pintype "passive"))
      (node (ref "R52") (pin "2") (pinfunction "2_2") (pintype "passive"))
      (node (ref "R57") (pin "1") (pinfunction "1_1") (pintype "passive"))
      (node (ref "R58") (pin "1") (pinfunction "1_1") (pintype "passive"))
      (node (ref "R59") (pin "1") (pinfunction "1_1") (pintype "passive"))
      (node (ref "R60") (pin "1") (pinfunction "1_1") (pintype "passive"))
      (node (ref "R66") (pin "2") (pinfunction "2_2") (pintype "passive"))
      (node (ref "R76") (pin "2") (pinfunction "2_2") (pintype "passive"))
      (node (ref "R79") (pin "2") (pinfunction "2_2") (pintype "passive"))
      (node (ref "XP10") (pin "4") (pinfunction "4_4") (pintype "passive"))
      (node (ref "XP11") (pin "2") (pinfunction "2_2") (pintype "passive"))
      (node (ref "XP3") (pin "1") (pinfunction "1_1") (pintype "passive"))
      (node (ref "XP4") (pin "1") (pinfunction "1_1") (pintype "passive"))
      (node (ref "XP9") (pin "3") (pinfunction "3_3") (pintype "passive"))
      (node (ref "XP9") (pin "5") (pinfunction "5_5") (pintype "passive"))
    )
    (net (code "4") (name "/+5VUSB") (class "Default")
      (node (ref "C31") (pin "2") (pinfunction "2_2") (pintype "passive"))
      (node (ref "DD2") (pin "7") (pinfunction "VREGIN_7") (pintype "power_in"))
      (node (ref "DD2") (pin "8") (pinfunction "VBUS_8") (pintype "passive"))
      (node (ref "X1") (pin "1") (pinfunction "VBUS_1") (pintype "passive"))
    )
    (net (code "5") (name "/+10V") (class "Default")
      (node (ref "C12") (pin "2") (pinfunction "2_2") (pintype "passive"))
      (node (ref "C14") (pin "2") (pinfunction "2_2") (pintype "passive"))
      (node (ref "C3") (pin "1") (pinfunction "1_1") (pintype "passive"))
      (node (ref "C7") (pin "2") (pinfunction "2_2") (pintype "passive"))
      (node (ref "DA5") (pin "3") (pinfunction "Vin_3") (pintype "passive"))
      (node (ref "DA6") (pin "3") (pinfunction "Vin_3") (pintype "passive"))
      (node (ref "DA8") (pin "3") (pinfunction "IN_3") (pintype "passive"))
      (node (ref "VD1") (pin "2") (pinfunction "K_2") (pintype "passive"))
      (node (ref "VD2") (pin "2") (pinfunction "K_2") (pintype "passive"))
      (node (ref "XP9") (pin "15") (pinfunction "15_15") (pintype "passive"))
    )
    (net (code "6") (name "/+24V") (class "Default")
      (node (ref "C19") (pin "1") (pinfunction "1_1") (pintype "passive"))
      (node (ref "K1") (pin "1") (pinfunction "1_1") (pintype "power_in"))
      (node (ref "K2") (pin "1") (pinfunction "1_1") (pintype "power_in"))
      (node (ref "VD3") (pin "1") (pinfunction "K_1") (pintype "passive"))
      (node (ref "VD4") (pin "3") (pinfunction "K_3") (pintype "passive"))
      (node (ref "XP5") (pin "1") (pinfunction "1_1") (pintype "passive"))
      (node (ref "XP7") (pin "7") (pinfunction "7_7") (pintype "passive"))
      (node (ref "XP9") (pin "2") (pinfunction "2_2") (pintype "passive"))
    )
    (net (code "7") (name "/ADD") (class "Default")
      (node (ref "R77") (pin "2") (pinfunction "2_2") (pintype "passive"))
      (node (ref "XP7") (pin "5") (pinfunction "5_5") (pintype "passive"))
    )
    (net (code "8") (name "/B1") (class "Default")
      (node (ref "R1") (pin "1") (pinfunction "1_1") (pintype "passive"))
      (node (ref "XP9") (pin "7") (pinfunction "7_7") (pintype "passive"))
    )
    (net (code "9") (name "/B1O") (class "Default")
      (node (ref "C2") (pin "2") (pinfunction "2_2") (pintype "passive"))
      (node (ref "DD1") (pin "25") (pinfunction "PC5_25") (pintype "passive"))
      (node (ref "R1") (pin "2") (pinfunction "2_2") (pintype "passive"))
    )
    (net (code "10") (name "/Boot") (class "Default")
      (node (ref "DD1") (pin "60") (pinfunction "BOOT_60") (pintype "passive"))
      (node (ref "R54") (pin "2") (pinfunction "2_2") (pintype "passive"))
      (node (ref "XP6") (pin "1") (pinfunction "1_1") (pintype "passive"))
    )
    (net (code "11") (name "/C2D") (class "Default")
      (node (ref "DD1") (pin "2") (pinfunction "PC13_2") (pintype "passive"))
      (node (ref "R75") (pin "2") (pinfunction "2_2") (pintype "passive"))
    )
    (net (code "12") (name "/CLA") (class "Default")
      (node (ref "C35") (pin "2") (pinfunction "2_2") (pintype "passive"))
      (node (ref "DD1") (pin "20") (pinfunction "PA4_20") (pintype "passive"))
      (node (ref "R50") (pin "1") (pinfunction "1_1") (pintype "passive"))
      (node (ref "R51") (pin "2") (pinfunction "2_2") (pintype "passive"))
    )
    (net (code "13") (name "/CLF") (class "Default")
      (node (ref "C32") (pin "2") (pinfunction "2_2") (pintype "passive"))
      (node (ref "DD1") (pin "27") (pinfunction "PB1_27") (pintype "passive"))
      (node (ref "R39") (pin "1") (pinfunction "1_1") (pintype "passive"))
      (node (ref "R43") (pin "2") (pinfunction "2_2") (pintype "passive"))
    )
    (net (code "14") (name "/CLK") (class "Default")
      (node (ref "XP9") (pin "11") (pinfunction "11_11") (pintype "passive"))
    )
    (net (code "15") (name "/CLKA") (class "Default")
      (node (ref "R51") (pin "1") (pinfunction "1_1") (pintype "passive"))
    )
    (net (code "16") (name "/CLKF") (class "Default")
      (node (ref "R43") (pin "1") (pinfunction "1_1") (pintype "passive"))
      (node (ref "R65") (pin "1") (pinfunction "1_1") (pintype "passive"))
    )
    (net (code "17") (name "/CMD_Screen") (class "Default")
      (node (ref "XP11") (pin "5") (pinfunction "5_5") (pintype "passive"))
    )
    (net (code "18") (name "/CNTRL") (class "Default")
      (node (ref "R67") (pin "2") (pinfunction "2_2") (pintype "passive"))
      (node (ref "XP7") (pin "6") (pinfunction "6_6") (pintype "passive"))
    )
    (net (code "19") (name "/COM") (class "Default")
      (node (ref "K1") (pin "4") (pinfunction "4_4") (pintype "power_in"))
      (node (ref "K2") (pin "4") (pinfunction "4_4") (pintype "power_in"))
      (node (ref "XP7") (pin "1") (pinfunction "1_1") (pintype "passive"))
    )
    (net (code "20") (name "/CS") (class "Default")
      (node (ref "R17") (pin "1") (pinfunction "1_1") (pintype "passive"))
      (node (ref "XP9") (pin "10") (pinfunction "10_10") (pintype "passive"))
    )
    (net (code "21") (name "/CS0") (class "Default")
      (node (ref "C11") (pin "2") (pinfunction "2_2") (pintype "passive"))
      (node (ref "R17") (pin "2") (pinfunction "2_2") (pintype "passive"))
    )
    (net (code "22") (name "/CS1") (class "Default")
      (node (ref "C17") (pin "2") (pinfunction "2_2") (pintype "passive"))
      (node (ref "DD1") (pin "26") (pinfunction "PB0_26") (pintype "passive"))
      (node (ref "R18") (pin "1") (pinfunction "1_1") (pintype "passive"))
      (node (ref "R20") (pin "2") (pinfunction "2_2") (pintype "passive"))
    )
    (net (code "23") (name "/CSNV") (class "Default")
      (node (ref "R20") (pin "1") (pinfunction "1_1") (pintype "passive"))
    )
    (net (code "24") (name "/DATA") (class "Default")
      (node (ref "R31") (pin "1") (pinfunction "1_1") (pintype "passive"))
      (node (ref "XP9") (pin "12") (pinfunction "12_12") (pintype "passive"))
    )
    (net (code "25") (name "/DAT_A") (class "Default")
      (node (ref "C22") (pin "2") (pinfunction "2_2") (pintype "passive"))
      (node (ref "DD1") (pin "28") (pinfunction "PB2_28") (pintype "passive"))
      (node (ref "R31") (pin "2") (pinfunction "2_2") (pintype "passive"))
      (node (ref "R79") (pin "1") (pinfunction "1_1") (pintype "passive"))
    )
    (net (code "26") (name "/DAT_F") (class "Default")
      (node (ref "C49") (pin "2") (pinfunction "2_2") (pintype "passive"))
      (node (ref "DD1") (pin "55") (pinfunction "PB3_55") (pintype "passive"))
      (node (ref "R27") (pin "1") (pinfunction "1_1") (pintype "passive"))
      (node (ref "R30") (pin "2") (pinfunction "2_2") (pintype "passive"))
    )
    (net (code "27") (name "/DI1") (class "Default")
      (node (ref "C39") (pin "1") (pinfunction "1_1") (pintype "passive"))
      (node (ref "DA14") (pin "4") (pinfunction "COLLECTOR_4") (pintype "passive"))
      (node (ref "DD1") (pin "51") (pinfunction "PC10_51") (pintype "passive"))
      (node (ref "R64") (pin "2") (pinfunction "2_2") (pintype "passive"))
      (node (ref "R66") (pin "1") (pinfunction "1_1") (pintype "passive"))
    )
    (net (code "28") (name "/DI2") (class "Default")
      (node (ref "DA15") (pin "4") (pinfunction "COLLECTOR_4") (pintype "passive"))
      (node (ref "DD1") (pin "15") (pinfunction "PA1_15") (pintype "passive"))
      (node (ref "R76") (pin "1") (pinfunction "1_1") (pintype "passive"))
    )
    (net (code "29") (name "/DO1") (class "Default")
      (node (ref "C37") (pin "1") (pinfunction "1_1") (pintype "passive"))
      (node (ref "DD1") (pin "24") (pinfunction "PC4_24") (pintype "passive"))
      (node (ref "R56") (pin "2") (pinfunction "2_2") (pintype "passive"))
      (node (ref "R73") (pin "1") (pinfunction "1_1") (pintype "passive"))
    )
    (net (code "30") (name "/DO2") (class "Default")
      (node (ref "C38") (pin "1") (pinfunction "1_1") (pintype "passive"))
      (node (ref "DD1") (pin "11") (pinfunction "PC3_11") (pintype "passive"))
      (node (ref "R61") (pin "2") (pinfunction "2_2") (pintype "passive"))
      (node (ref "R74") (pin "1") (pinfunction "1_1") (pintype "passive"))
    )
    (net (code "31") (name "/DTIN") (class "Default")
      (node (ref "R25") (pin "2") (pinfunction "2_2") (pintype "passive"))
      (node (ref "R40") (pin "2") (pinfunction "2_2") (pintype "passive"))
      (node (ref "XP9") (pin "6") (pinfunction "6_6") (pintype "passive"))
    )
    (net (code "32") (name "/DTNV") (class "Default")
      (node (ref "R30") (pin "1") (pinfunction "1_1") (pintype "passive"))
      (node (ref "R68") (pin "1") (pinfunction "1_1") (pintype "passive"))
    )
    (net (code "33") (name "/FAN") (class "Default")
      (node (ref "C42") (pin "2") (pinfunction "2_2") (pintype "passive"))
      (node (ref "DA14") (pin "1") (pinfunction "A_1") (pintype "passive"))
      (node (ref "R55") (pin "2") (pinfunction "2_2") (pintype "passive"))
      (node (ref "R67") (pin "1") (pinfunction "1_1") (pintype "passive"))
      (node (ref "R70") (pin "2") (pinfunction "2_2") (pintype "passive"))
      (node (ref "VT2") (pin "1") (pinfunction "G_1") (pintype "passive"))
    )
    (net (code "34") (name "/FRCS") (class "Default")
      (node (ref "DD1") (pin "40") (pinfunction "PC9_40") (pintype "passive"))
      (node (ref "R71") (pin "1") (pinfunction "1_1") (pintype "passive"))
    )
    (net (code "35") (name "/GND1") (class "Default")
      (node (ref "C19") (pin "2") (pinfunction "2_2") (pintype "passive"))
      (node (ref "C28") (pin "2") (pinfunction "2_2") (pintype "passive"))
      (node (ref "C29") (pin "1") (pinfunction "1_1") (pintype "passive"))
      (node (ref "C30") (pin "1") (pinfunction "1_1") (pintype "passive"))
      (node (ref "C31") (pin "1") (pinfunction "1_1") (pintype "passive"))
      (node (ref "DA11") (pin "5") (pinfunction "GND_5") (pintype "passive"))
      (node (ref "DA12") (pin "3") (pinfunction "EMITTER_3") (pintype "passive"))
      (node (ref "DA13") (pin "3") (pinfunction "EMITTER_3") (pintype "passive"))
      (node (ref "DD2") (pin "0") (pinfunction "UGND_0") (pintype "power_in"))
      (node (ref "DD2") (pin "2") (pinfunction "UGND_2") (pintype "power_in"))
      (node (ref "DD2") (pin "29") (pinfunction "I_29") (pintype "power_in"))
      (node (ref "R55") (pin "1") (pinfunction "1_1") (pintype "passive"))
      (node (ref "VD3") (pin "2") (pinfunction "A_2") (pintype "passive"))
      (node (ref "VD6") (pin "3") (pinfunction "K_3") (pintype "passive"))
      (node (ref "VT2") (pin "2") (pinfunction "D_2") (pintype "passive"))
      (node (ref "X1") (pin "4") (pinfunction "VGND_4") (pintype "passive"))
      (node (ref "X1") (pin "5") (pinfunction "s_5") (pintype "power_in"))
      (node (ref "X1") (pin "6") (pinfunction "s_6") (pintype "power_in"))
      (node (ref "XP7") (pin "4") (pinfunction "4_4") (pintype "passive"))
      (node (ref "XP9") (pin "1") (pinfunction "1_1") (pintype "passive"))
      (node (ref "XP9") (pin "4") (pinfunction "4_4") (pintype "passive"))
    )
    (net (code "36") (name "/I2C_SCL") (class "Default")
      (node (ref "DD1") (pin "58") (pinfunction "PB6_58") (pintype "passive"))
      (node (ref "XP11") (pin "7") (pinfunction "7_7") (pintype "passive"))
    )
    (net (code "37") (name "/I2C_SDA") (class "Default")
      (node (ref "DD1") (pin "59") (pinfunction "PB7_59") (pintype "passive"))
      (node (ref "XP11") (pin "9") (pinfunction "9_9") (pintype "passive"))
    )
    (net (code "38") (name "/Io") (class "Default")
      (node (ref "C33") (pin "2") (pinfunction "2_2") (pintype "passive"))
      (node (ref "DA4") (pin "7") (pinfunction "OUT_7") (pintype "passive"))
      (node (ref "R35") (pin "1") (pinfunction "1_1") (pintype "passive"))
    )
    (net (code "39") (name "/Iomax") (class "Default")
      (node (ref "C20") (pin "2") (pinfunction "2_2") (pintype "passive"))
      (node (ref "DA3") (pin "7") (pinfunction "OUT_7") (pintype "passive"))
      (node (ref "R23") (pin "1") (pinfunction "1_1") (pintype "passive"))
    )
    (net (code "40") (name "/LED1") (class "Default")
      (node (ref "C43") (pin "1") (pinfunction "1_1") (pintype "passive"))
      (node (ref "DD1") (pin "52") (pinfunction "PC11_52") (pintype "passive"))
      (node (ref "R69") (pin "2") (pinfunction "2_2") (pintype "passive"))
    )
    (net (code "41") (name "/LED2") (class "Default")
      (node (ref "C44") (pin "1") (pinfunction "1_1") (pintype "passive"))
      (node (ref "DD1") (pin "53") (pinfunction "PC12_53") (pintype "passive"))
      (node (ref "R72") (pin "2") (pinfunction "2_2") (pintype "passive"))
    )
    (net (code "42") (name "/MSR") (class "Default")
      (node (ref "R10") (pin "1") (pinfunction "1_1") (pintype "passive"))
      (node (ref "XP9") (pin "13") (pinfunction "13_13") (pintype "passive"))
    )
    (net (code "43") (name "/MSRO") (class "Default")
      (node (ref "C6") (pin "2") (pinfunction "2_2") (pintype "passive"))
      (node (ref "DD1") (pin "39") (pinfunction "PC8_39") (pintype "passive"))
      (node (ref "R10") (pin "2") (pinfunction "2_2") (pintype "passive"))
    )
    (net (code "44") (name "/RG") (class "Default")
      (node (ref "K1") (pin "3") (pinfunction "3_3") (pintype "power_in"))
      (node (ref "XP7") (pin "2") (pinfunction "2_2") (pintype "passive"))
    )
    (net (code "45") (name "/RK") (class "Default")
      (node (ref "K2") (pin "3") (pinfunction "3_3") (pintype "power_in"))
      (node (ref "XP7") (pin "3") (pinfunction "3_3") (pintype "passive"))
    )
    (net (code "46") (name "/RX1") (class "Default")
      (node (ref "DD1") (pin "43") (pinfunction "PA10_43") (pintype "passive"))
      (node (ref "XP3") (pin "3") (pinfunction "3_3") (pintype "passive"))
    )
    (net (code "47") (name "/RX2") (class "Default")
      (node (ref "DA10") (pin "4") (pinfunction "OUT_4") (pintype "output"))
      (node (ref "DD1") (pin "17") (pinfunction "PA3_17") (pintype "passive"))
      (node (ref "R36") (pin "1") (pinfunction "1_1") (pintype "passive"))
      (node (ref "XP4") (pin "3") (pinfunction "3_3") (pintype "passive"))
    )
    (net (code "48") (name "/RX3") (class "Default")
      (node (ref "DD1") (pin "30") (pinfunction "PB11_30") (pintype "passive"))
    )
    (net (code "49") (name "/Reset") (class "Default")
      (node (ref "C34") (pin "2") (pinfunction "2_2") (pintype "passive"))
      (node (ref "DD1") (pin "7") (pinfunction "SR_7") (pintype "passive"))
      (node (ref "R49") (pin "1") (pinfunction "1_1") (pintype "passive"))
      (node (ref "XP2") (pin "2") (pinfunction "2_2") (pintype "passive"))
    )
    (net (code "50") (name "/Rng") (class "Default")
      (node (ref "VT1") (pin "1") (pinfunction "G_1") (pintype "passive"))
    )
    (net (code "51") (name "/S0") (class "Default")
      (node (ref "DD1") (pin "3") (pinfunction "PC14_3") (pintype "passive"))
      (node (ref "SA1") (pin "2") (pinfunction "2_2") (pintype "passive"))
    )
    (net (code "52") (name "/S1") (class "Default")
      (node (ref "DD1") (pin "4") (pinfunction "PC15_4") (pintype "passive"))
      (node (ref "SA1") (pin "4") (pinfunction "4_4") (pintype "passive"))
    )
    (net (code "53") (name "/S2") (class "Default")
      (node (ref "DD1") (pin "33") (pinfunction "PB12_33") (pintype "passive"))
      (node (ref "SA1") (pin "6") (pinfunction "6_6") (pintype "passive"))
    )
    (net (code "54") (name "/S3") (class "Default")
      (node (ref "DD1") (pin "34") (pinfunction "PB13_34") (pintype "passive"))
      (node (ref "SA1") (pin "8") (pinfunction "8_8") (pintype "passive"))
    )
    (net (code "55") (name "/S4") (class "Default")
      (node (ref "C36") (pin "2") (pinfunction "2_2") (pintype "passive"))
      (node (ref "DD1") (pin "22") (pinfunction "PA6_22") (pintype "passive"))
      (node (ref "DD1") (pin "35") (pinfunction "PB14_35") (pintype "passive"))
      (node (ref "R52") (pin "1") (pinfunction "1_1") (pintype "passive"))
      (node (ref "SB1") (pin "2") (pinfunction "2_2") (pintype "passive"))
    )
    (net (code "56") (name "/SC1") (class "Default")
      (node (ref "R63") (pin "1") (pinfunction "1_1") (pintype "passive"))
      (node (ref "XP9") (pin "16") (pinfunction "16_16") (pintype "passive"))
    )
    (net (code "57") (name "/SC2") (class "Default")
      (node (ref "R62") (pin "1") (pinfunction "1_1") (pintype "passive"))
      (node (ref "XP9") (pin "14") (pinfunction "14_14") (pintype "passive"))
    )
    (net (code "58") (name "/SC_1") (class "Default")
      (node (ref "C41") (pin "2") (pinfunction "2_2") (pintype "passive"))
      (node (ref "DD1") (pin "37") (pinfunction "PC6_37") (pintype "passive"))
      (node (ref "DD1") (pin "44") (pinfunction "PA11_44") (pintype "passive"))
      (node (ref "R63") (pin "2") (pinfunction "2_2") (pintype "passive"))
    )
    (net (code "59") (name "/SC_2") (class "Default")
      (node (ref "C40") (pin "2") (pinfunction "2_2") (pintype "passive"))
      (node (ref "DD1") (pin "38") (pinfunction "PC7_38") (pintype "passive"))
      (node (ref "DD1") (pin "45") (pinfunction "PA12_45") (pintype "passive"))
      (node (ref "R62") (pin "2") (pinfunction "2_2") (pintype "passive"))
    )
    (net (code "60") (name "/SPI_MOSI") (class "Default")
      (node (ref "DD1") (pin "23") (pinfunction "PA7_23") (pintype "passive"))
      (node (ref "XP11") (pin "3") (pinfunction "3_3") (pintype "passive"))
    )
    (net (code "61") (name "/SPI_SCK") (class "Default")
      (node (ref "DD1") (pin "21") (pinfunction "PA5_21") (pintype "passive"))
      (node (ref "XP11") (pin "1") (pinfunction "1_1") (pintype "passive"))
    )
    (net (code "62") (name "/SWCLK") (class "Default")
      (node (ref "DD1") (pin "49") (pinfunction "PA14_49") (pintype "passive"))
      (node (ref "XP10") (pin "2") (pinfunction "2_2") (pintype "passive"))
    )
    (net (code "63") (name "/SWDIO") (class "Default")
      (node (ref "DD1") (pin "46") (pinfunction "PA13_46") (pintype "passive"))
      (node (ref "XP10") (pin "3") (pinfunction "3_3") (pintype "passive"))
    )
    (net (code "64") (name "/SYNC") (class "Default")
      (node (ref "C8") (pin "2") (pinfunction "2_2") (pintype "passive"))
      (node (ref "DA2") (pin "1") (pinfunction "OUT_1") (pintype "passive"))
      (node (ref "DD1") (pin "14") (pinfunction "PA0_14") (pintype "passive"))
      (node (ref "R7") (pin "1") (pinfunction "1_1") (pintype "passive"))
    )
    (net (code "65") (name "/TX1") (class "Default")
      (node (ref "DD1") (pin "42") (pinfunction "PA9_42") (pintype "passive"))
      (node (ref "XP3") (pin "2") (pinfunction "2_2") (pintype "passive"))
    )
    (net (code "66") (name "/TX2") (class "Default")
      (node (ref "DA11") (pin "2") (pinfunction "K_2") (pintype "passive"))
      (node (ref "DD1") (pin "16") (pinfunction "PA2_16") (pintype "passive"))
      (node (ref "XP4") (pin "2") (pinfunction "2_2") (pintype "passive"))
    )
    (net (code "67") (name "/TX3") (class "Default")
      (node (ref "DD1") (pin "29") (pinfunction "PB10_29") (pintype "passive"))
    )
    (net (code "68") (name "/US") (class "Default")
      (node (ref "R11") (pin "1") (pinfunction "1_1") (pintype "passive"))
      (node (ref "TV1") (pin "20") (pinfunction "20_20") (pintype "passive"))
    )
    (net (code "69") (name "/USB+") (class "Default")
      (node (ref "DD2") (pin "3") (pinfunction "D+_3") (pintype "passive"))
      (node (ref "X1") (pin "3") (pinfunction "D+_3") (pintype "passive"))
    )
    (net (code "70") (name "/USB-") (class "Default")
      (node (ref "DD2") (pin "4") (pinfunction "D-_4") (pintype "passive"))
      (node (ref "X1") (pin "2") (pinfunction "D-_2") (pintype "passive"))
    )
    (net (code "71") (name "GND") (class "Default")
      (node (ref "C1") (pin "1") (pinfunction "1_1") (pintype "passive"))
      (node (ref "C10") (pin "2") (pinfunction "2_2") (pintype "passive"))
      (node (ref "C11") (pin "1") (pinfunction "1_1") (pintype "passive"))
      (node (ref "C12") (pin "1") (pinfunction "1_1") (pintype "passive"))
      (node (ref "C13") (pin "1") (pinfunction "1_1") (pintype "passive"))
      (node (ref "C14") (pin "1") (pinfunction "1_1") (pintype "passive"))
      (node (ref "C15") (pin "1") (pinfunction "1_1") (pintype "passive"))
      (node (ref "C16") (pin "2") (pinfunction "2_2") (pintype "passive"))
      (node (ref "C17") (pin "1") (pinfunction "1_1") (pintype "passive"))
      (node (ref "C18") (pin "1") (pinfunction "1_1") (pintype "passive"))
      (node (ref "C2") (pin "1") (pinfunction "1_1") (pintype "passive"))
      (node (ref "C20") (pin "1") (pinfunction "1_1") (pintype "passive"))
      (node (ref "C21") (pin "1") (pinfunction "1_1") (pintype "passive"))
      (node (ref "C22") (pin "1") (pinfunction "1_1") (pintype "passive"))
      (node (ref "C23") (pin "1") (pinfunction "1_1") (pintype "passive"))
      (node (ref "C24") (pin "1") (pinfunction "1_1") (pintype "passive"))
      (node (ref "C25") (pin "1") (pinfunction "1_1") (pintype "passive"))
      (node (ref "C26") (pin "1") (pinfunction "1_1") (pintype "passive"))
      (node (ref "C27") (pin "1") (pinfunction "1_1") (pintype "passive"))
      (node (ref "C3") (pin "2") (pinfunction "2_2") (pintype "passive"))
      (node (ref "C32") (pin "1") (pinfunction "1_1") (pintype "passive"))
      (node (ref "C33") (pin "1") (pinfunction "1_1") (pintype "passive"))
      (node (ref "C34") (pin "1") (pinfunction "1_1") (pintype "passive"))
      (node (ref "C35") (pin "1") (pinfunction "1_1") (pintype "passive"))
      (node (ref "C36") (pin "1") (pinfunction "1_1") (pintype "passive"))
      (node (ref "C37") (pin "2") (pinfunction "2_2") (pintype "passive"))
      (node (ref "C38") (pin "2") (pinfunction "2_2") (pintype "passive"))
      (node (ref "C39") (pin "2") (pinfunction "2_2") (pintype "passive"))
      (node (ref "C4") (pin "1") (pinfunction "1_1") (pintype "passive"))
      (node (ref "C40") (pin "1") (pinfunction "1_1") (pintype "passive"))
      (node (ref "C41") (pin "1") (pinfunction "1_1") (pintype "passive"))
      (node (ref "C43") (pin "2") (pinfunction "2_2") (pintype "passive"))
      (node (ref "C44") (pin "2") (pinfunction "2_2") (pintype "passive"))
      (node (ref "C45") (pin "2") (pinfunction "2_2") (pintype "passive"))
      (node (ref "C47") (pin "1") (pinfunction "1_1") (pintype "passive"))
      (node (ref "C48") (pin "1") (pinfunction "1_1") (pintype "passive"))
      (node (ref "C49") (pin "1") (pinfunction "1_1") (pintype "passive"))
      (node (ref "C5") (pin "2") (pinfunction "2_2") (pintype "passive"))
      (node (ref "C50") (pin "2") (pinfunction "2_2") (pintype "passive"))
      (node (ref "C51") (pin "2") (pinfunction "2_2") (pintype "passive"))
      (node (ref "C6") (pin "1") (pinfunction "1_1") (pintype "passive"))
      (node (ref "C7") (pin "1") (pinfunction "1_1") (pintype "passive"))
      (node (ref "C8") (pin "1") (pinfunction "1_1") (pintype "passive"))
      (node (ref "C9") (pin "1") (pinfunction "1_1") (pintype "passive"))
      (node (ref "DA1") (pin "4") (pinfunction "-V_4") (pintype "power_in"))
      (node (ref "DA10") (pin "5") (pinfunction "GND_5") (pintype "passive"))
      (node (ref "DA14") (pin "3") (pinfunction "EMITTER_3") (pintype "passive"))
      (node (ref "DA15") (pin "3") (pinfunction "EMITTER_3") (pintype "passive"))
      (node (ref "DA2") (pin "4") (pinfunction "-V_4") (pintype "power_in"))
      (node (ref "DA2") (pin "5") (pinfunction "IN+_5") (pintype "passive"))
      (node (ref "DA3") (pin "4") (pinfunction "-V_4") (pintype "power_in"))
      (node (ref "DA4") (pin "4") (pinfunction "-V_4") (pintype "power_in"))
      (node (ref "DA5") (pin "0") (pinfunction "GND_0") (pintype "passive"))
      (node (ref "DA5") (pin "2") (pinfunction "GND_2") (pintype "passive"))
      (node (ref "DA6") (pin "0") (pinfunction "GND_0") (pintype "passive"))
      (node (ref "DA6") (pin "2") (pinfunction "GND_2") (pintype "passive"))
      (node (ref "DA8") (pin "1") (pinfunction "GND_1") (pintype "passive"))
      (node (ref "DD1") (pin "12") (pinfunction "AGND_12") (pintype "passive"))
      (node (ref "DD1") (pin "18") (pinfunction "GND_18") (pintype "passive"))
      (node (ref "DD1") (pin "63") (pinfunction "GND_63") (pintype "passive"))
      (node (ref "R14") (pin "2") (pinfunction "2_2") (pintype "passive"))
      (node (ref "R15") (pin "1") (pinfunction "1_1") (pintype "passive"))
      (node (ref "R16") (pin "1") (pinfunction "1_1") (pintype "passive"))
      (node (ref "R28") (pin "2") (pinfunction "2_2") (pintype "passive"))
      (node (ref "R29") (pin "1") (pinfunction "1_1") (pintype "passive"))
      (node (ref "R46") (pin "1") (pinfunction "1_1") (pintype "passive"))
      (node (ref "R47") (pin "2") (pinfunction "2_2") (pintype "passive"))
      (node (ref "R53") (pin "2") (pinfunction "2_2") (pintype "passive"))
      (node (ref "R54") (pin "1") (pinfunction "1_1") (pintype "passive"))
      (node (ref "SA1") (pin "1") (pinfunction "1_1") (pintype "passive"))
      (node (ref "SA1") (pin "3") (pinfunction "3_3") (pintype "passive"))
      (node (ref "SA1") (pin "5") (pinfunction "5_5") (pintype "passive"))
      (node (ref "SA1") (pin "7") (pinfunction "7_7") (pintype "passive"))
      (node (ref "SB1") (pin "1") (pinfunction "1_1") (pintype "passive"))
      (node (ref "TV1") (pin "13") (pinfunction "13_13") (pintype "passive"))
      (node (ref "TV1") (pin "18") (pinfunction "18_18") (pintype "passive"))
      (node (ref "VT1") (pin "2") (pinfunction "D_2") (pintype "passive"))
      (node (ref "XP10") (pin "1") (pinfunction "1_1") (pintype "passive"))
      (node (ref "XP11") (pin "10") (pinfunction "10_10") (pintype "passive"))
      (node (ref "XP11") (pin "6") (pinfunction "6_6") (pintype "passive"))
      (node (ref "XP11") (pin "8") (pinfunction "8_8") (pintype "passive"))
      (node (ref "XP2") (pin "1") (pinfunction "1_1") (pintype "passive"))
      (node (ref "XP3") (pin "4") (pinfunction "4_4") (pintype "passive"))
      (node (ref "XP4") (pin "4") (pinfunction "4_4") (pintype "passive"))
      (node (ref "XP8") (pin "1") (pinfunction "1_1") (pintype "passive"))
      (node (ref "XP8") (pin "10") (pinfunction "10_10") (pintype "passive"))
      (node (ref "XP9") (pin "8") (pinfunction "8_8") (pintype "passive"))
      (node (ref "XP9") (pin "9") (pinfunction "9_9") (pintype "passive"))
    )
    (net (code "72") (name "Net-(DA1A-IN+)") (class "Default")
      (node (ref "DA1") (pin "3") (pinfunction "IN+_3") (pintype "passive"))
      (node (ref "R14") (pin "1") (pinfunction "1_1") (pintype "passive"))
      (node (ref "R4") (pin "2") (pinfunction "2_2") (pintype "passive"))
    )
    (net (code "73") (name "Net-(DA1A-IN-)") (class "Default")
      (node (ref "DA1") (pin "2") (pinfunction "IN-_2") (pintype "passive"))
      (node (ref "R11") (pin "2") (pinfunction "2_2") (pintype "passive"))
      (node (ref "R5") (pin "2") (pinfunction "2_2") (pintype "passive"))
    )
    (net (code "74") (name "Net-(DA1A-OUT)") (class "Default")
      (node (ref "DA1") (pin "1") (pinfunction "OUT_1") (pintype "passive"))
      (node (ref "R12") (pin "2") (pinfunction "2_2") (pintype "passive"))
      (node (ref "R5") (pin "1") (pinfunction "1_1") (pintype "passive"))
    )
    (net (code "75") (name "Net-(DA1B-IN+)") (class "Default")
      (node (ref "DA1") (pin "5") (pinfunction "IN+_5") (pintype "passive"))
      (node (ref "R15") (pin "2") (pinfunction "2_2") (pintype "passive"))
      (node (ref "R8") (pin "2") (pinfunction "2_2") (pintype "passive"))
    )
    (net (code "76") (name "Net-(DA1B-IN-)") (class "Default")
      (node (ref "DA1") (pin "6") (pinfunction "IN-_6") (pintype "passive"))
      (node (ref "R12") (pin "1") (pinfunction "1_1") (pintype "passive"))
      (node (ref "R6") (pin "2") (pinfunction "2_2") (pintype "passive"))
    )
    (net (code "77") (name "Net-(DA1B-OUT)") (class "Default")
      (node (ref "DA1") (pin "7") (pinfunction "OUT_7") (pintype "passive"))
      (node (ref "R13") (pin "2") (pinfunction "2_2") (pintype "passive"))
      (node (ref "R6") (pin "1") (pinfunction "1_1") (pintype "passive"))
    )
    (net (code "78") (name "Net-(DA2A-IN+)") (class "Default")
      (node (ref "DA2") (pin "3") (pinfunction "IN+_3") (pintype "passive"))
      (node (ref "R16") (pin "2") (pinfunction "2_2") (pintype "passive"))
      (node (ref "R9") (pin "2") (pinfunction "2_2") (pintype "passive"))
    )
    (net (code "79") (name "Net-(DA2A-IN-)") (class "Default")
      (node (ref "DA2") (pin "2") (pinfunction "IN-_2") (pintype "passive"))
      (node (ref "R13") (pin "1") (pinfunction "1_1") (pintype "passive"))
      (node (ref "R7") (pin "2") (pinfunction "2_2") (pintype "passive"))
    )
    (net (code "80") (name "Net-(DA2B-IN-)") (class "Default")
      (node (ref "DA2") (pin "6") (pinfunction "IN-_6") (pintype "passive"))
      (node (ref "DA2") (pin "7") (pinfunction "OUT_7") (pintype "passive"))
    )
    (net (code "81") (name "Net-(DA3A-IN+)") (class "Default")
      (node (ref "DA3") (pin "3") (pinfunction "IN+_3") (pintype "passive"))
      (node (ref "R21") (pin "2") (pinfunction "2_2") (pintype "passive"))
      (node (ref "R28") (pin "1") (pinfunction "1_1") (pintype "passive"))
    )
    (net (code "82") (name "Net-(DA3A-IN-)") (class "Default")
      (node (ref "DA3") (pin "2") (pinfunction "IN-_2") (pintype "passive"))
      (node (ref "R22") (pin "2") (pinfunction "2_2") (pintype "passive"))
      (node (ref "R25") (pin "1") (pinfunction "1_1") (pintype "passive"))
    )
    (net (code "83") (name "Net-(DA3A-OUT)") (class "Default")
      (node (ref "DA3") (pin "1") (pinfunction "OUT_1") (pintype "passive"))
      (node (ref "R22") (pin "1") (pinfunction "1_1") (pintype "passive"))
      (node (ref "R26") (pin "2") (pinfunction "2_2") (pintype "passive"))
    )
    (net (code "84") (name "Net-(DA3B-IN+)") (class "Default")
      (node (ref "DA3") (pin "5") (pinfunction "IN+_5") (pintype "passive"))
      (node (ref "R24") (pin "2") (pinfunction "2_2") (pintype "passive"))
      (node (ref "R29") (pin "2") (pinfunction "2_2") (pintype "passive"))
    )
    (net (code "85") (name "Net-(DA3B-IN-)") (class "Default")
      (node (ref "DA3") (pin "6") (pinfunction "IN-_6") (pintype "passive"))
      (node (ref "R23") (pin "2") (pinfunction "2_2") (pintype "passive"))
      (node (ref "R26") (pin "1") (pinfunction "1_1") (pintype "passive"))
    )
    (net (code "86") (name "Net-(DA4A-IN+)") (class "Default")
      (node (ref "DA4") (pin "3") (pinfunction "IN+_3") (pintype "passive"))
      (node (ref "R33") (pin "2") (pinfunction "2_2") (pintype "passive"))
      (node (ref "R47") (pin "1") (pinfunction "1_1") (pintype "passive"))
    )
    (net (code "87") (name "Net-(DA4A-IN-)") (class "Default")
      (node (ref "DA4") (pin "2") (pinfunction "IN-_2") (pintype "passive"))
      (node (ref "R34") (pin "2") (pinfunction "2_2") (pintype "passive"))
      (node (ref "R40") (pin "1") (pinfunction "1_1") (pintype "passive"))
    )
    (net (code "88") (name "Net-(DA4A-OUT)") (class "Default")
      (node (ref "DA4") (pin "1") (pinfunction "OUT_1") (pintype "passive"))
      (node (ref "R34") (pin "1") (pinfunction "1_1") (pintype "passive"))
      (node (ref "R41") (pin "2") (pinfunction "2_2") (pintype "passive"))
    )
    (net (code "89") (name "Net-(DA4B-IN+)") (class "Default")
      (node (ref "DA4") (pin "5") (pinfunction "IN+_5") (pintype "passive"))
      (node (ref "R37") (pin "2") (pinfunction "2_2") (pintype "passive"))
      (node (ref "R46") (pin "2") (pinfunction "2_2") (pintype "passive"))
    )
    (net (code "90") (name "Net-(DA4B-IN-)") (class "Default")
      (node (ref "DA4") (pin "6") (pinfunction "IN-_6") (pintype "passive"))
      (node (ref "R35") (pin "2") (pinfunction "2_2") (pintype "passive"))
      (node (ref "R41") (pin "1") (pinfunction "1_1") (pintype "passive"))
      (node (ref "R45") (pin "2") (pinfunction "2_2") (pintype "passive"))
    )
    (net (code "91") (name "Net-(DA10-A)") (class "Default")
      (node (ref "C28") (pin "1") (pinfunction "1_1") (pintype "passive"))
      (node (ref "C29") (pin "2") (pinfunction "2_2") (pintype "passive"))
      (node (ref "C30") (pin "2") (pinfunction "2_2") (pintype "passive"))
      (node (ref "DA10") (pin "1") (pinfunction "A_1") (pintype "passive"))
      (node (ref "DA11") (pin "6") (pinfunction "VCC_6") (pintype "passive"))
      (node (ref "DD2") (pin "5") (pinfunction "VIO_5") (pintype "power_in"))
      (node (ref "DD2") (pin "6") (pinfunction "VDIN_6") (pintype "power_in"))
      (node (ref "R38") (pin "2") (pinfunction "2_2") (pintype "passive"))
      (node (ref "R48") (pin "2") (pinfunction "2_2") (pintype "passive"))
    )
    (net (code "92") (name "Net-(DA10-K)") (class "Default")
      (node (ref "DA10") (pin "2") (pinfunction "K_2") (pintype "passive"))
      (node (ref "R42") (pin "2") (pinfunction "2_2") (pintype "passive"))
    )
    (net (code "93") (name "Net-(DA11-A)") (class "Default")
      (node (ref "DA11") (pin "1") (pinfunction "A_1") (pintype "passive"))
      (node (ref "R44") (pin "1") (pinfunction "1_1") (pintype "passive"))
    )
    (net (code "94") (name "Net-(DA11-OUT)") (class "Default")
      (node (ref "DA11") (pin "4") (pinfunction "OUT_4") (pintype "output"))
      (node (ref "DD2") (pin "24") (pinfunction "RXD_24") (pintype "passive"))
      (node (ref "R48") (pin "1") (pinfunction "1_1") (pintype "passive"))
    )
    (net (code "95") (name "Net-(DA12-COLLECTOR)") (class "Default")
      (node (ref "DA12") (pin "4") (pinfunction "COLLECTOR_4") (pintype "passive"))
      (node (ref "K1") (pin "2") (pinfunction "2_2") (pintype "power_in"))
      (node (ref "VD4") (pin "2") (pinfunction "A2_2") (pintype "passive"))
    )
    (net (code "96") (name "Net-(DA12-K)") (class "Default")
      (node (ref "DA12") (pin "2") (pinfunction "K_2") (pintype "passive"))
      (node (ref "R73") (pin "2") (pinfunction "2_2") (pintype "passive"))
    )
    (net (code "97") (name "Net-(DA13-COLLECTOR)") (class "Default")
      (node (ref "DA13") (pin "4") (pinfunction "COLLECTOR_4") (pintype "passive"))
      (node (ref "K2") (pin "2") (pinfunction "2_2") (pintype "power_in"))
      (node (ref "VD4") (pin "1") (pinfunction "A1_1") (pintype "passive"))
    )
    (net (code "98") (name "Net-(DA13-K)") (class "Default")
      (node (ref "DA13") (pin "2") (pinfunction "K_2") (pintype "passive"))
      (node (ref "R74") (pin "2") (pinfunction "2_2") (pintype "passive"))
    )
    (net (code "99") (name "Net-(DA14-K)") (class "Default")
      (node (ref "DA14") (pin "2") (pinfunction "K_2") (pintype "passive"))
      (node (ref "R70") (pin "1") (pinfunction "1_1") (pintype "passive"))
      (node (ref "VD5") (pin "2") (pinfunction "K_2") (pintype "passive"))
    )
    (net (code "100") (name "Net-(DA15-A)") (class "Default")
      (node (ref "C46") (pin "2") (pinfunction "2_2") (pintype "passive"))
      (node (ref "DA15") (pin "1") (pinfunction "A_1") (pintype "passive"))
      (node (ref "R77") (pin "1") (pinfunction "1_1") (pintype "passive"))
      (node (ref "R78") (pin "2") (pinfunction "2_2") (pintype "passive"))
    )
    (net (code "101") (name "Net-(DA15-K)") (class "Default")
      (node (ref "DA15") (pin "2") (pinfunction "K_2") (pintype "passive"))
      (node (ref "R78") (pin "1") (pinfunction "1_1") (pintype "passive"))
      (node (ref "VD7") (pin "2") (pinfunction "K_2") (pintype "passive"))
    )
    (net (code "102") (name "Net-(DD1-VCAP_1)") (class "Default")
      (node (ref "C18") (pin "2") (pinfunction "2_2") (pintype "passive"))
      (node (ref "DD1") (pin "31") (pinfunction "VCAP_1_31") (pintype "passive"))
    )
    (net (code "103") (name "Net-(DD1-VCAP_2)") (class "Default")
      (node (ref "C21") (pin "2") (pinfunction "2_2") (pintype "passive"))
      (node (ref "DD1") (pin "47") (pinfunction "VCAP_2_47") (pintype "passive"))
    )
    (net (code "104") (name "Net-(DD2-TXD)") (class "Default")
      (node (ref "DD2") (pin "25") (pinfunction "TXD_25") (pintype "passive"))
      (node (ref "R42") (pin "1") (pinfunction "1_1") (pintype "passive"))
    )
    (net (code "105") (name "Net-(DD2-~{RS}T)") (class "Default")
      (node (ref "DD2") (pin "9") (pinfunction "~{RS}T_9") (pintype "passive"))
      (node (ref "R38") (pin "1") (pinfunction "1_1") (pintype "passive"))
    )
    (net (code "106") (name "Net-(FU1-Pad1)") (class "Default")
      (node (ref "FU1") (pin "1") (pinfunction "1_1") (pintype "passive"))
      (node (ref "TV1") (pin "7") (pinfunction "7_7") (pintype "passive"))
    )
    (net (code "107") (name "Net-(FU1-Pad2)") (class "Default")
      (node (ref "FU1") (pin "2") (pinfunction "2_2") (pintype "passive"))
      (node (ref "TV1") (pin "2") (pinfunction "2_2") (pintype "passive"))
    )
    (net (code "108") (name "Net-(FU2-Pad1)") (class "Default")
      (node (ref "FU2") (pin "1") (pinfunction "1_1") (pintype "passive"))
      (node (ref "TV1") (pin "6") (pinfunction "6_6") (pintype "passive"))
    )
    (net (code "109") (name "Net-(FU2-Pad2)") (class "Default")
      (node (ref "FU2") (pin "2") (pinfunction "2_2") (pintype "passive"))
      (node (ref "TV1") (pin "1") (pinfunction "1_1") (pintype "passive"))
    )
    (net (code "110") (name "Net-(HL1-K)") (class "Default")
      (node (ref "HL1") (pin "2") (pinfunction "K_2") (pintype "passive"))
      (node (ref "R53") (pin "1") (pinfunction "1_1") (pintype "passive"))
    )
    (net (code "111") (name "Net-(HL2-K)") (class "Default")
      (node (ref "HL2") (pin "2") (pinfunction "K_2") (pintype "passive"))
      (node (ref "R56") (pin "1") (pinfunction "1_1") (pintype "passive"))
    )
    (net (code "112") (name "Net-(HL3-K)") (class "Default")
      (node (ref "HL3") (pin "2") (pinfunction "K_2") (pintype "passive"))
      (node (ref "R61") (pin "1") (pinfunction "1_1") (pintype "passive"))
    )
    (net (code "113") (name "Net-(HL4-K)") (class "Default")
      (node (ref "HL4") (pin "2") (pinfunction "K_2") (pintype "passive"))
      (node (ref "R64") (pin "1") (pinfunction "1_1") (pintype "passive"))
    )
    (net (code "114") (name "Net-(HL5-K)") (class "Default")
      (node (ref "HL5") (pin "2") (pinfunction "K_2") (pintype "passive"))
      (node (ref "R69") (pin "1") (pinfunction "1_1") (pintype "passive"))
    )
    (net (code "115") (name "Net-(HL6-K)") (class "Default")
      (node (ref "HL6") (pin "2") (pinfunction "K_2") (pintype "passive"))
      (node (ref "R72") (pin "1") (pinfunction "1_1") (pintype "passive"))
    )
    (net (code "116") (name "Net-(HL7-K)") (class "Default")
      (node (ref "C45") (pin "1") (pinfunction "1_1") (pintype "passive"))
      (node (ref "HL7") (pin "2") (pinfunction "K_2") (pintype "passive"))
      (node (ref "R75") (pin "1") (pinfunction "1_1") (pintype "passive"))
    )
    (net (code "117") (name "Net-(R2-Pad2)") (class "Default")
      (node (ref "R2") (pin "2") (pinfunction "2_2") (pintype "passive"))
      (node (ref "R8") (pin "1") (pinfunction "1_1") (pintype "passive"))
    )
    (net (code "118") (name "Net-(R3-Pad2)") (class "Default")
      (node (ref "R3") (pin "2") (pinfunction "2_2") (pintype "passive"))
      (node (ref "R9") (pin "1") (pinfunction "1_1") (pintype "passive"))
    )
    (net (code "119") (name "Net-(R19-Pad2)") (class "Default")
      (node (ref "R19") (pin "2") (pinfunction "2_2") (pintype "passive"))
      (node (ref "R24") (pin "1") (pinfunction "1_1") (pintype "passive"))
    )
    (net (code "120") (name "Net-(R32-Pad2)") (class "Default")
      (node (ref "R32") (pin "2") (pinfunction "2_2") (pintype "passive"))
      (node (ref "R37") (pin "1") (pinfunction "1_1") (pintype "passive"))
    )
    (net (code "121") (name "Net-(R57-Pad2)") (class "Default")
      (node (ref "R57") (pin "2") (pinfunction "2_2") (pintype "passive"))
      (node (ref "XP8") (pin "2") (pinfunction "2_2") (pintype "passive"))
      (node (ref "XP8") (pin "9") (pinfunction "9_9") (pintype "passive"))
    )
    (net (code "122") (name "Net-(R58-Pad2)") (class "Default")
      (node (ref "R58") (pin "2") (pinfunction "2_2") (pintype "passive"))
      (node (ref "R65") (pin "2") (pinfunction "2_2") (pintype "passive"))
      (node (ref "XP8") (pin "3") (pinfunction "3_3") (pintype "passive"))
      (node (ref "XP8") (pin "8") (pinfunction "8_8") (pintype "passive"))
    )
    (net (code "123") (name "Net-(R59-Pad2)") (class "Default")
      (node (ref "R59") (pin "2") (pinfunction "2_2") (pintype "passive"))
      (node (ref "R68") (pin "2") (pinfunction "2_2") (pintype "passive"))
      (node (ref "XP8") (pin "5") (pinfunction "5_5") (pintype "passive"))
      (node (ref "XP8") (pin "6") (pinfunction "6_6") (pintype "passive"))
    )
    (net (code "124") (name "Net-(R60-Pad2)") (class "Default")
      (node (ref "R60") (pin "2") (pinfunction "2_2") (pintype "passive"))
      (node (ref "R71") (pin "2") (pinfunction "2_2") (pintype "passive"))
      (node (ref "XP8") (pin "4") (pinfunction "4_4") (pintype "passive"))
      (node (ref "XP8") (pin "7") (pinfunction "7_7") (pintype "passive"))
    )
    (net (code "125") (name "Net-(TV1-Pad4)") (class "Default")
      (node (ref "TV1") (pin "4") (pinfunction "4_4") (pintype "passive"))
      (node (ref "XP1") (pin "1") (pinfunction "1_1") (pintype "passive"))
      (node (ref "XP1") (pin "2") (pinfunction "2_2") (pintype "passive"))
    )
    (net (code "126") (name "Net-(TV1-Pad9)") (class "Default")
      (node (ref "TV1") (pin "9") (pinfunction "9_9") (pintype "passive"))
      (node (ref "XP1") (pin "10") (pinfunction "10_10") (pintype "passive"))
      (node (ref "XP1") (pin "9") (pinfunction "9_9") (pintype "passive"))
    )
    (net (code "127") (name "Net-(TV1-Pad11)") (class "Default")
      (node (ref "TV1") (pin "11") (pinfunction "11_11") (pintype "passive"))
      (node (ref "VD3") (pin "4") (pinfunction "C_4") (pintype "passive"))
    )
    (net (code "128") (name "Net-(TV1-Pad12)") (class "Default")
      (node (ref "TV1") (pin "12") (pinfunction "12_12") (pintype "passive"))
      (node (ref "TV1") (pin "17") (pinfunction "17_17") (pintype "passive"))
    )
    (net (code "129") (name "Net-(TV1-Pad16)") (class "Default")
      (node (ref "TV1") (pin "16") (pinfunction "16_16") (pintype "passive"))
      (node (ref "VD3") (pin "3") (pinfunction "C_3") (pintype "passive"))
    )
    (net (code "130") (name "Net-(VD1-A)") (class "Default")
      (node (ref "TV1") (pin "19") (pinfunction "19_19") (pintype "passive"))
      (node (ref "VD1") (pin "1") (pinfunction "A_1") (pintype "passive"))
    )
    (net (code "131") (name "Net-(VD2-A)") (class "Default")
      (node (ref "TV1") (pin "14") (pinfunction "14_14") (pintype "passive"))
      (node (ref "VD2") (pin "1") (pinfunction "A_1") (pintype "passive"))
    )
    (net (code "132") (name "Net-(VD5-A)") (class "Default")
      (node (ref "C42") (pin "1") (pinfunction "1_1") (pintype "passive"))
      (node (ref "VD5") (pin "1") (pinfunction "A_1") (pintype "passive"))
      (node (ref "VD6") (pin "2") (pinfunction "A2_2") (pintype "passive"))
    )
    (net (code "133") (name "Net-(VD6A-A1)") (class "Default")
      (node (ref "C46") (pin "1") (pinfunction "1_1") (pintype "passive"))
      (node (ref "VD6") (pin "1") (pinfunction "A1_1") (pintype "passive"))
      (node (ref "VD7") (pin "1") (pinfunction "A_1") (pintype "passive"))
    )
    (net (code "134") (name "Net-(VT1-S)") (class "Default")
      (node (ref "R45") (pin "1") (pinfunction "1_1") (pintype "passive"))
      (node (ref "VT1") (pin "3") (pinfunction "S_3") (pintype "passive"))
    )
    (net (code "135") (name "Net-(VT2-S)") (class "Default")
      (node (ref "VT2") (pin "3") (pinfunction "S_3") (pintype "passive"))
      (node (ref "XP5") (pin "2") (pinfunction "2_2") (pintype "passive"))
    )
    (net (code "136") (name "Net-(Y1-L1)") (class "Default")
      (node (ref "C51") (pin "1") (pinfunction "1_1") (pintype "passive"))
      (node (ref "R80") (pin "1") (pinfunction "1_1") (pintype "passive"))
      (node (ref "Y1") (pin "1") (pinfunction "L1_1") (pintype "passive"))
    )
    (net (code "137") (name "Net-(Y1-L2)") (class "Default")
      (node (ref "C50") (pin "1") (pinfunction "1_1") (pintype "passive"))
      (node (ref "R80") (pin "2") (pinfunction "2_2") (pintype "passive"))
      (node (ref "Y1") (pin "2") (pinfunction "L2_2") (pintype "passive"))
    )
    (net (code "138") (name "VDIN") (class "Default")
      (node (ref "DD2") (pin "10") (pinfunction "VDIN_10") (pintype "power_in"))
      (node (ref "DD2") (pin "13") (pinfunction "VDIN_13") (pintype "power_in"))
      (node (ref "DD2") (pin "14") (pinfunction "VDIN_14") (pintype "power_in"))
      (node (ref "DD2") (pin "15") (pinfunction "VDIN_15") (pintype "power_in"))
      (node (ref "DD2") (pin "20") (pinfunction "VDIN_20") (pintype "power_in"))
      (node (ref "DD2") (pin "21") (pinfunction "VDIN_21") (pintype "power_in"))
    )
    (net (code "139") (name "unconnected-(DD1-PA8-Pad41)") (class "Default")
      (node (ref "DD1") (pin "41") (pinfunction "PA8_41") (pintype "passive"))
    )
    (net (code "140") (name "unconnected-(DD1-PA15-Pad50)") (class "Default")
      (node (ref "DD1") (pin "50") (pinfunction "PA15_50") (pintype "passive"))
    )
    (net (code "141") (name "unconnected-(DD1-PB4-Pad56)") (class "Default")
      (node (ref "DD1") (pin "56") (pinfunction "PB4_56") (pintype "passive"))
    )
    (net (code "142") (name "unconnected-(DD1-PB5-Pad57)") (class "Default")
      (node (ref "DD1") (pin "57") (pinfunction "PB5_57") (pintype "output"))
    )
    (net (code "143") (name "unconnected-(DD1-PB8-Pad61)") (class "Default")
      (node (ref "DD1") (pin "61") (pinfunction "PB8_61") (pintype "passive"))
    )
    (net (code "144") (name "unconnected-(DD1-PB9-Pad62)") (class "Default")
      (node (ref "DD1") (pin "62") (pinfunction "PB9_62") (pintype "passive"))
    )
    (net (code "145") (name "unconnected-(DD1-PB15-Pad36)") (class "Default")
      (node (ref "DD1") (pin "36") (pinfunction "PB15_36") (pintype "passive"))
    )
    (net (code "146") (name "unconnected-(DD1-PC0-Pad8)") (class "Default")
      (node (ref "DD1") (pin "8") (pinfunction "PC0_8") (pintype "passive"))
    )
    (net (code "147") (name "unconnected-(DD1-PC1-Pad9)") (class "Default")
      (node (ref "DD1") (pin "9") (pinfunction "PC1_9") (pintype "passive"))
    )
    (net (code "148") (name "unconnected-(DD1-PC2-Pad10)") (class "Default")
      (node (ref "DD1") (pin "10") (pinfunction "PC2_10") (pintype "passive"))
    )
    (net (code "149") (name "unconnected-(DD1-PD2-Pad54)") (class "Default")
      (node (ref "DD1") (pin "54") (pinfunction "PD2_54") (pintype "passive"))
    )
    (net (code "150") (name "unconnected-(DD1-PH0-Pad5)") (class "Default")
      (node (ref "DD1") (pin "5") (pinfunction "PH0_5") (pintype "passive"))
    )
    (net (code "151") (name "unconnected-(DD1-PH1-Pad6)") (class "Default")
      (node (ref "DD1") (pin "6") (pinfunction "PH1_6") (pintype "passive"))
    )
    (net (code "152") (name "unconnected-(DD2-CTS-Pad22)") (class "Default")
      (node (ref "DD2") (pin "22") (pinfunction "CTS_22") (pintype "passive"))
    )
    (net (code "153") (name "unconnected-(DD2-DCD-Pad28)") (class "Default")
      (node (ref "DD2") (pin "28") (pinfunction "DCD_28") (pintype "passive"))
    )
    (net (code "154") (name "unconnected-(DD2-DSR-Pad26)") (class "Default")
      (node (ref "DD2") (pin "26") (pinfunction "DSR_26") (pintype "passive"))
    )
    (net (code "155") (name "unconnected-(DD2-DTR-Pad27)") (class "Default")
      (node (ref "DD2") (pin "27") (pinfunction "DTR_27") (pintype "passive"))
    )
    (net (code "156") (name "unconnected-(DD2-GPIO0-Pad19)") (class "Default")
      (node (ref "DD2") (pin "19") (pinfunction "GPIO0_19") (pintype "passive"))
    )
    (net (code "157") (name "unconnected-(DD2-GPIO1-Pad18)") (class "Default")
      (node (ref "DD2") (pin "18") (pinfunction "GPIO1_18") (pintype "passive"))
    )
    (net (code "158") (name "unconnected-(DD2-GPIO2-Pad17)") (class "Default")
      (node (ref "DD2") (pin "17") (pinfunction "GPIO2_17") (pintype "passive"))
    )
    (net (code "159") (name "unconnected-(DD2-GPIO3-Pad16)") (class "Default")
      (node (ref "DD2") (pin "16") (pinfunction "GPIO3_16") (pintype "passive"))
    )
    (net (code "160") (name "unconnected-(DD2-RI-Pad1)") (class "Default")
      (node (ref "DD2") (pin "1") (pinfunction "RI_1") (pintype "passive"))
    )
    (net (code "161") (name "unconnected-(DD2-RTS-Pad23)") (class "Default")
      (node (ref "DD2") (pin "23") (pinfunction "RTS_23") (pintype "passive"))
    )
    (net (code "162") (name "unconnected-(DD2-SUSPEND-Pad12)") (class "Default")
      (node (ref "DD2") (pin "12") (pinfunction "SUSPEND_12") (pintype "passive"))
    )
    (net (code "163") (name "unconnected-(DD2-~{SUSPEND}-Pad11)") (class "Default")
      (node (ref "DD2") (pin "11") (pinfunction "~{SUSPEND}_11") (pintype "passive"))
    )
    (net (code "164") (name "unconnected-(TV1-Pad15)") (class "Default")
      (node (ref "TV1") (pin "15") (pinfunction "15_15") (pintype "passive"))
    )
    (net (code "165") (name "unconnected-(XP1-Pad3)") (class "Default")
      (node (ref "XP1") (pin "3") (pinfunction "3_3") (pintype "passive"))
    )
    (net (code "166") (name "unconnected-(XP1-Pad4)") (class "Default")
      (node (ref "XP1") (pin "4") (pinfunction "4_4") (pintype "passive"))
    )
    (net (code "167") (name "unconnected-(XP1-Pad5)") (class "Default")
      (node (ref "XP1") (pin "5") (pinfunction "5_5") (pintype "passive"))
    )
    (net (code "168") (name "unconnected-(XP1-Pad6)") (class "Default")
      (node (ref "XP1") (pin "6") (pinfunction "6_6") (pintype "passive"))
    )
    (net (code "169") (name "unconnected-(XP1-Pad7)") (class "Default")
      (node (ref "XP1") (pin "7") (pinfunction "7_7") (pintype "passive"))
    )
    (net (code "170") (name "unconnected-(XP1-Pad8)") (class "Default")
      (node (ref "XP1") (pin "8") (pinfunction "8_8") (pintype "passive"))
    )
  )
)
